# homeboard5.net
KiCad netlist of a schematic drawn in EAGLE
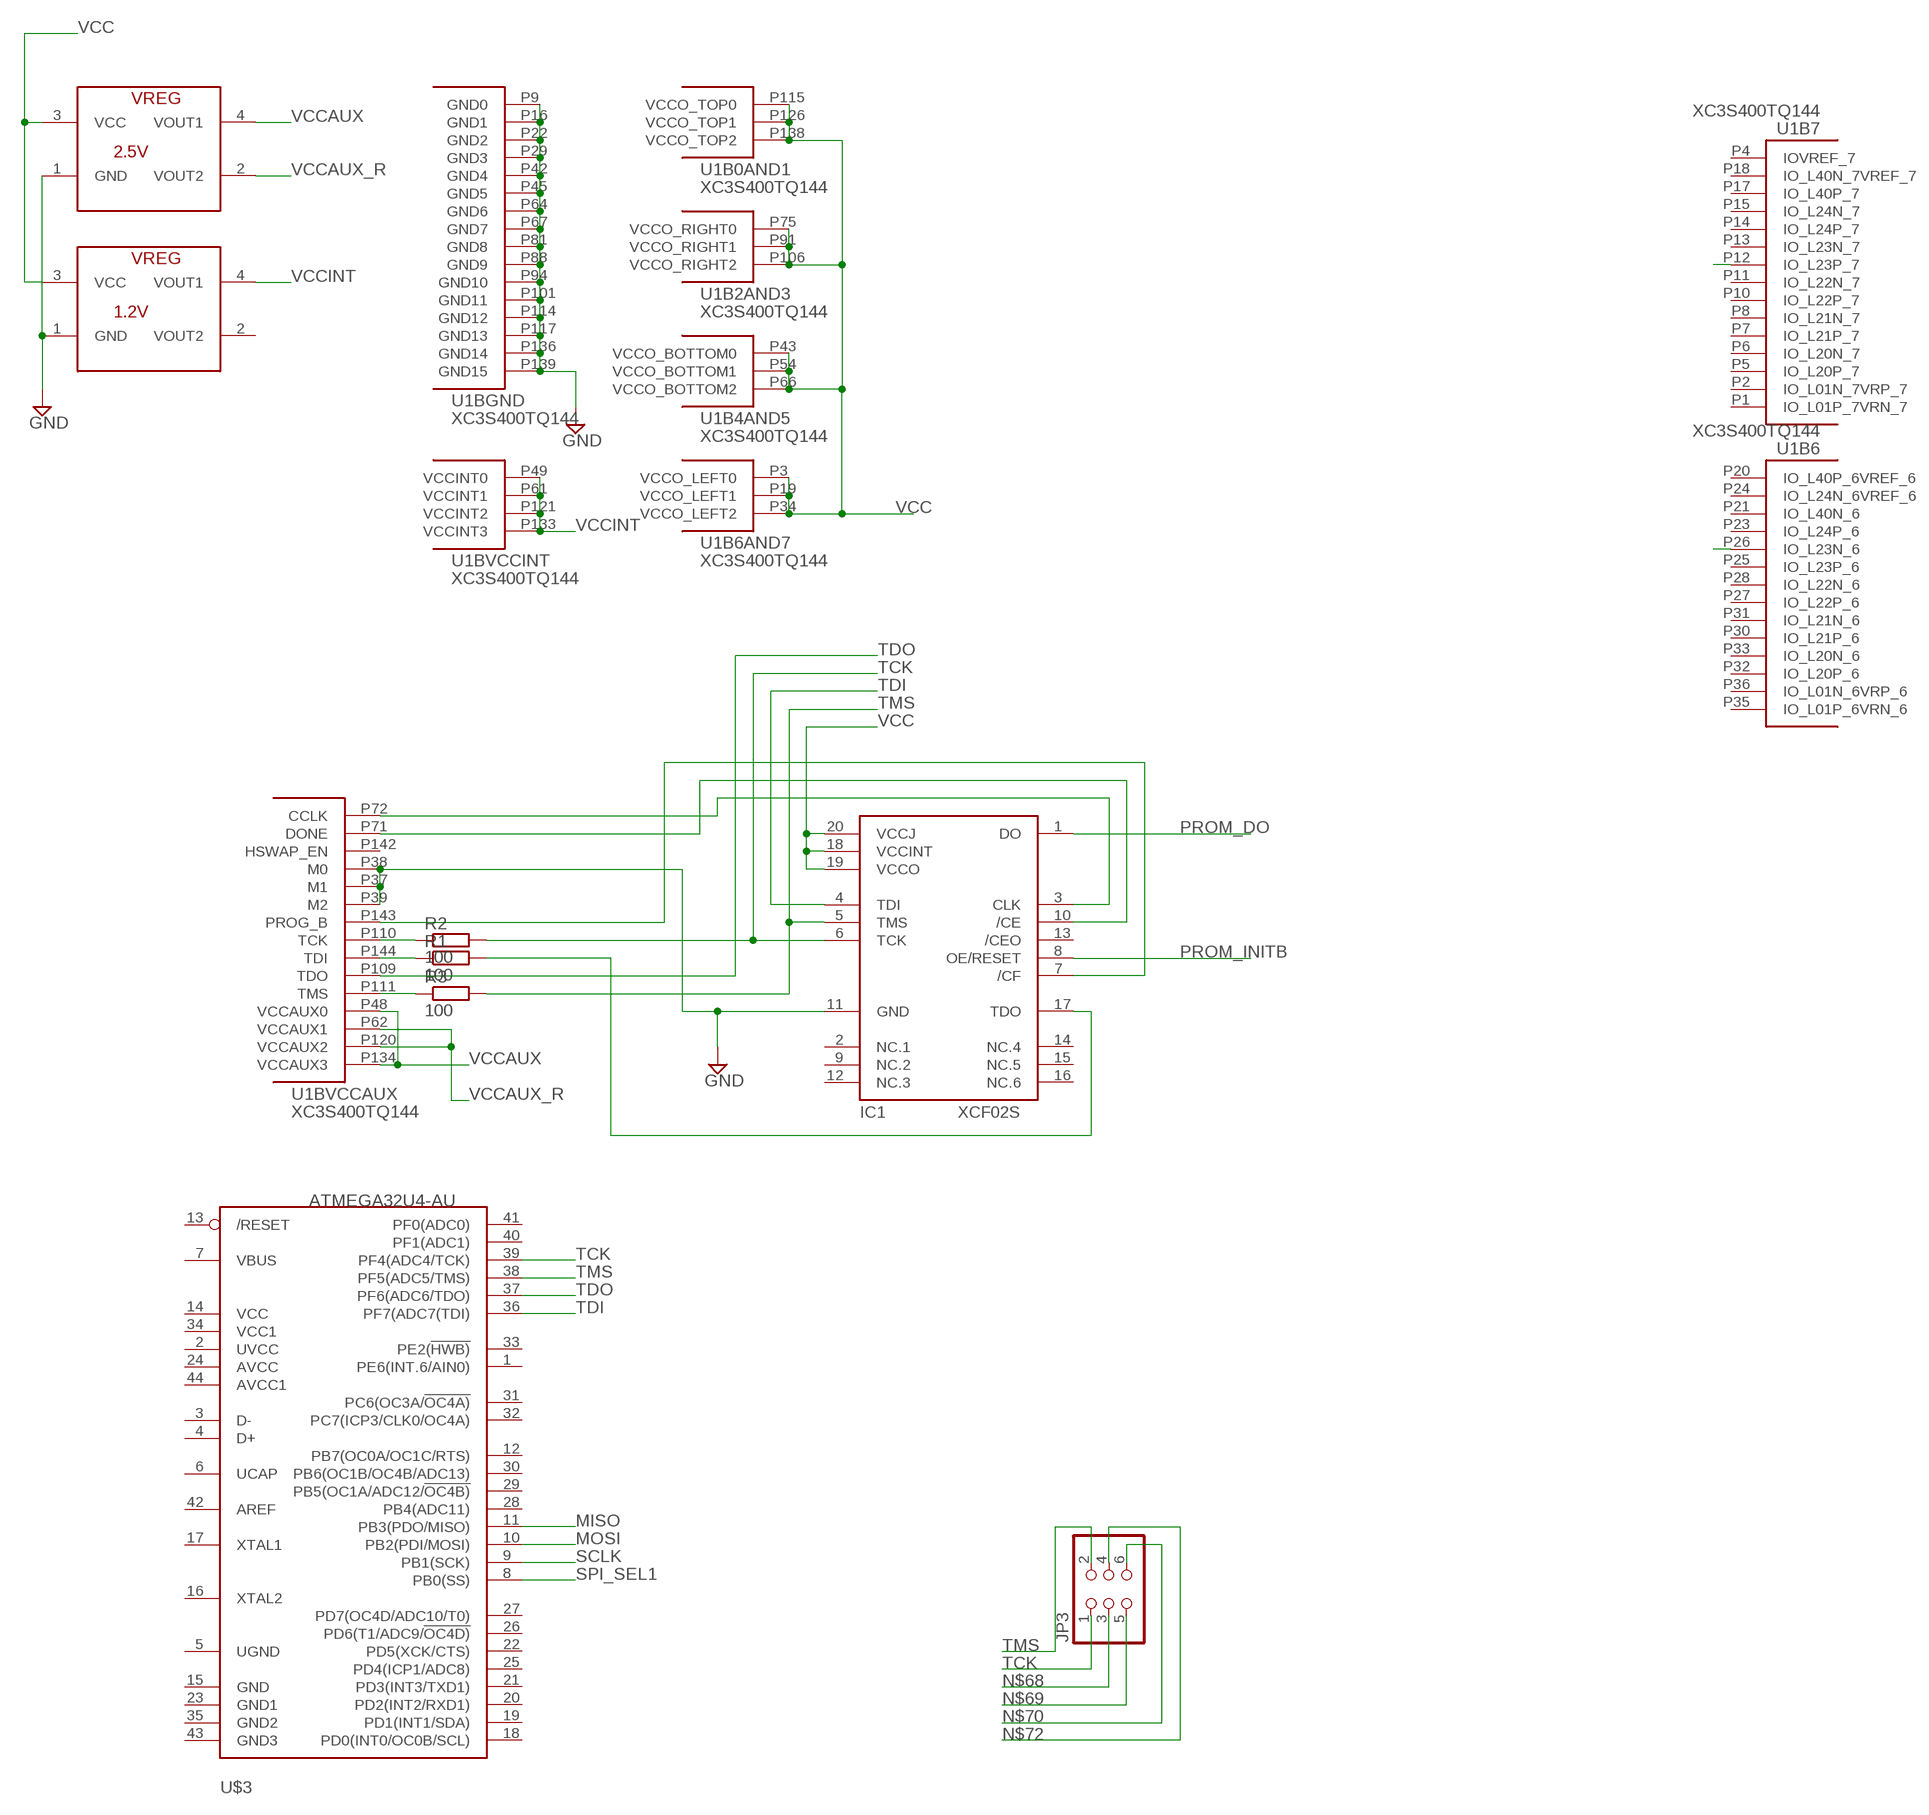
[diagram p0: schematic, sheet 1, part 1 of 3]
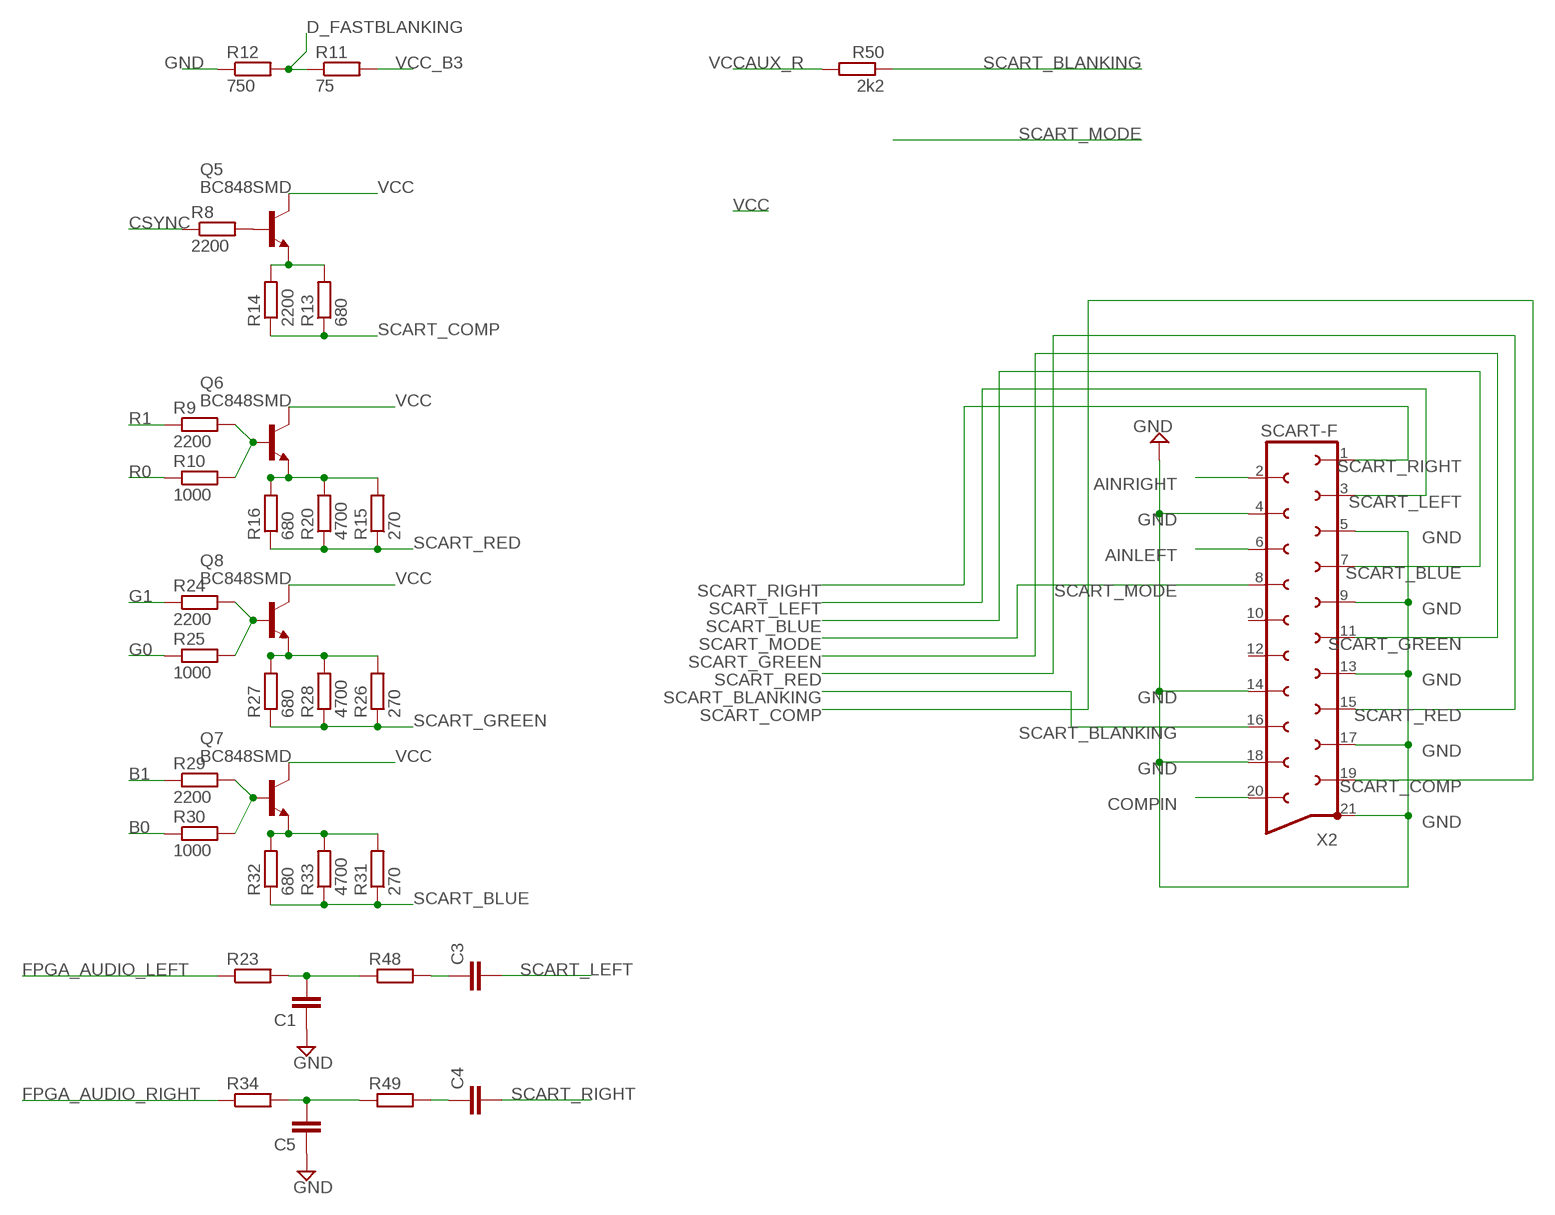
[diagram p1: schematic, sheet 1, part 2 of 3]
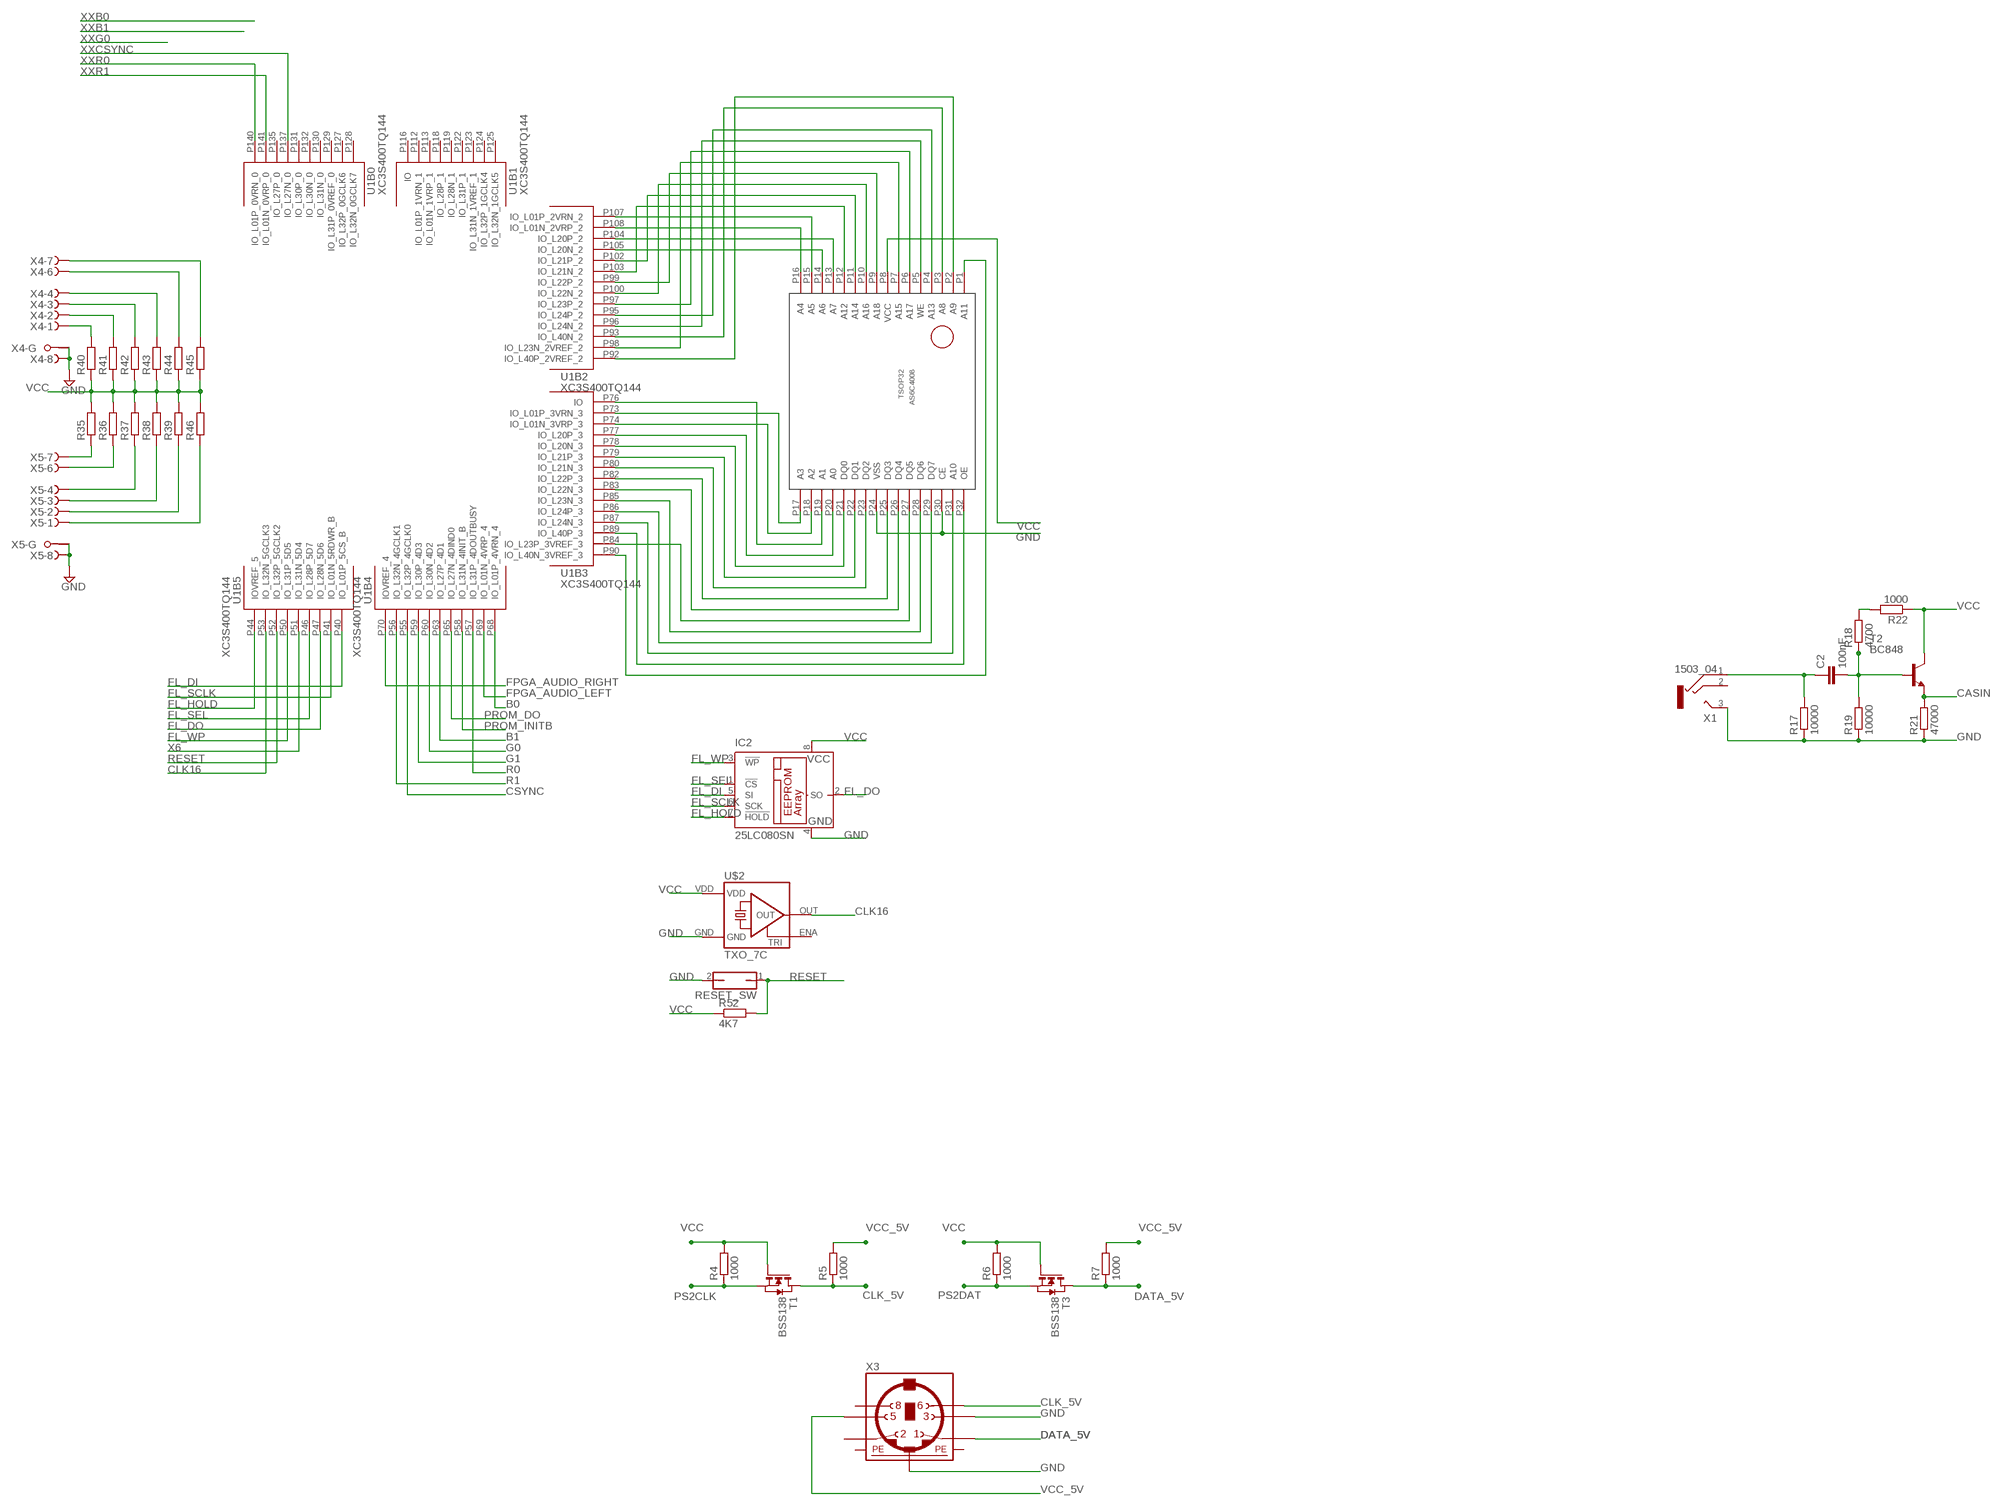
[diagram p2: schematic, sheet 1, part 3 of 3]

(export (version "E")
  (design (tool "Eeschema 10.0.6"))
  (components
    (comp (ref "C1")
      (value "C-EUC0603")
      (footprint "eagle-import:C0603")
      (libsource (lib "eagle-import") (part "C-EUC0603"))
    )
    (comp (ref "C2")
      (value "100nF")
      (footprint "eagle-import:C0603")
      (libsource (lib "eagle-import") (part "C-EUC0603"))
    )
    (comp (ref "C3")
      (value "C-EUC0603")
      (footprint "eagle-import:C0603")
      (libsource (lib "eagle-import") (part "C-EUC0603"))
    )
    (comp (ref "C4")
      (value "C-EUC0603")
      (footprint "eagle-import:C0603")
      (libsource (lib "eagle-import") (part "C-EUC0603"))
    )
    (comp (ref "C5")
      (value "C-EUC0603")
      (footprint "eagle-import:C0603")
      (libsource (lib "eagle-import") (part "C-EUC0603"))
    )
    (comp (ref "IC1")
      (value "XCF02S")
      (footprint "eagle-import:VO20")
      (libsource (lib "eagle-import") (part "XCF02S"))
    )
    (comp (ref "IC2")
      (value "25LC080SN")
      (footprint "eagle-import:SO-08")
      (fields (field (name "MF") "MICROCHIP") (field (name "MPN") "25LC080/SN"))
      (libsource (lib "eagle-import") (part "25SNLC080"))
    )
    (comp (ref "JP3")
      (value "PINHD-2X3")
      (footprint "eagle-import:2X03")
      (libsource (lib "eagle-import") (part "PINHD-2X3"))
    )
    (comp (ref "Q5")
      (value "BC848SMD")
      (footprint "eagle-import:SOT23")
      (libsource (lib "eagle-import") (part "BC848SMD"))
    )
    (comp (ref "Q6")
      (value "BC848SMD")
      (footprint "eagle-import:SOT23")
      (libsource (lib "eagle-import") (part "BC848SMD"))
    )
    (comp (ref "Q7")
      (value "BC848SMD")
      (footprint "eagle-import:SOT23")
      (libsource (lib "eagle-import") (part "BC848SMD"))
    )
    (comp (ref "Q8")
      (value "BC848SMD")
      (footprint "eagle-import:SOT23")
      (libsource (lib "eagle-import") (part "BC848SMD"))
    )
    (comp (ref "R1")
      (value "100")
      (footprint "eagle-import:R0805")
      (libsource (lib "eagle-import") (part "R-EU_R0805"))
    )
    (comp (ref "R2")
      (value "100")
      (footprint "eagle-import:R0805")
      (libsource (lib "eagle-import") (part "R-EU_R0805"))
    )
    (comp (ref "R3")
      (value "100")
      (footprint "eagle-import:R0805")
      (libsource (lib "eagle-import") (part "R-EU_R0805"))
    )
    (comp (ref "R4")
      (value "1000")
      (footprint "eagle-import:R0805")
      (libsource (lib "eagle-import") (part "R-EU_R0805"))
    )
    (comp (ref "R5")
      (value "1000")
      (footprint "eagle-import:R0805")
      (libsource (lib "eagle-import") (part "R-EU_R0805"))
    )
    (comp (ref "R6")
      (value "1000")
      (footprint "eagle-import:R0805")
      (libsource (lib "eagle-import") (part "R-EU_R0805"))
    )
    (comp (ref "R7")
      (value "1000")
      (footprint "eagle-import:R0805")
      (libsource (lib "eagle-import") (part "R-EU_R0805"))
    )
    (comp (ref "R8")
      (value "2200")
      (footprint "eagle-import:R0805")
      (libsource (lib "eagle-import") (part "R-EU_R0805"))
    )
    (comp (ref "R9")
      (value "2200")
      (footprint "eagle-import:R0805")
      (libsource (lib "eagle-import") (part "R-EU_R0805"))
    )
    (comp (ref "R10")
      (value "1000")
      (footprint "eagle-import:R0805")
      (libsource (lib "eagle-import") (part "R-EU_R0805"))
    )
    (comp (ref "R11")
      (value "75")
      (footprint "eagle-import:R0805")
      (libsource (lib "eagle-import") (part "R-EU_R0805"))
    )
    (comp (ref "R12")
      (value "750")
      (footprint "eagle-import:R0805")
      (libsource (lib "eagle-import") (part "R-EU_R0805"))
    )
    (comp (ref "R13")
      (value "680")
      (footprint "eagle-import:R0805")
      (libsource (lib "eagle-import") (part "R-EU_R0805"))
    )
    (comp (ref "R14")
      (value "2200")
      (footprint "eagle-import:R0805")
      (libsource (lib "eagle-import") (part "R-EU_R0805"))
    )
    (comp (ref "R15")
      (value "270")
      (footprint "eagle-import:R0805")
      (libsource (lib "eagle-import") (part "R-EU_R0805"))
    )
    (comp (ref "R16")
      (value "680")
      (footprint "eagle-import:R0805")
      (libsource (lib "eagle-import") (part "R-EU_R0805"))
    )
    (comp (ref "R17")
      (value "10000")
      (footprint "eagle-import:R0805")
      (libsource (lib "eagle-import") (part "R-EU_R0805"))
    )
    (comp (ref "R18")
      (value "4700")
      (footprint "eagle-import:R0805")
      (libsource (lib "eagle-import") (part "R-EU_R0805"))
    )
    (comp (ref "R19")
      (value "10000")
      (footprint "eagle-import:R0805")
      (libsource (lib "eagle-import") (part "R-EU_R0805"))
    )
    (comp (ref "R20")
      (value "4700")
      (footprint "eagle-import:R0805")
      (libsource (lib "eagle-import") (part "R-EU_R0805"))
    )
    (comp (ref "R21")
      (value "47000")
      (footprint "eagle-import:R0805")
      (libsource (lib "eagle-import") (part "R-EU_R0805"))
    )
    (comp (ref "R22")
      (value "1000")
      (footprint "eagle-import:R0805")
      (libsource (lib "eagle-import") (part "R-EU_R0805"))
    )
    (comp (ref "R23")
      (value "R-EU_M0805")
      (footprint "eagle-import:M0805")
      (libsource (lib "eagle-import") (part "resistor_R-EU_M0805"))
    )
    (comp (ref "R24")
      (value "2200")
      (footprint "eagle-import:R0805")
      (libsource (lib "eagle-import") (part "R-EU_R0805"))
    )
    (comp (ref "R25")
      (value "1000")
      (footprint "eagle-import:R0805")
      (libsource (lib "eagle-import") (part "R-EU_R0805"))
    )
    (comp (ref "R26")
      (value "270")
      (footprint "eagle-import:R0805")
      (libsource (lib "eagle-import") (part "R-EU_R0805"))
    )
    (comp (ref "R27")
      (value "680")
      (footprint "eagle-import:R0805")
      (libsource (lib "eagle-import") (part "R-EU_R0805"))
    )
    (comp (ref "R28")
      (value "4700")
      (footprint "eagle-import:R0805")
      (libsource (lib "eagle-import") (part "R-EU_R0805"))
    )
    (comp (ref "R29")
      (value "2200")
      (footprint "eagle-import:R0805")
      (libsource (lib "eagle-import") (part "R-EU_R0805"))
    )
    (comp (ref "R30")
      (value "1000")
      (footprint "eagle-import:R0805")
      (libsource (lib "eagle-import") (part "R-EU_R0805"))
    )
    (comp (ref "R31")
      (value "270")
      (footprint "eagle-import:R0805")
      (libsource (lib "eagle-import") (part "R-EU_R0805"))
    )
    (comp (ref "R32")
      (value "680")
      (footprint "eagle-import:R0805")
      (libsource (lib "eagle-import") (part "R-EU_R0805"))
    )
    (comp (ref "R33")
      (value "4700")
      (footprint "eagle-import:R0805")
      (libsource (lib "eagle-import") (part "R-EU_R0805"))
    )
    (comp (ref "R34")
      (value "R-EU_M0805")
      (footprint "eagle-import:M0805")
      (libsource (lib "eagle-import") (part "resistor_R-EU_M0805"))
    )
    (comp (ref "R35")
      (value "R-EU_M0805")
      (footprint "eagle-import:M0805")
      (libsource (lib "eagle-import") (part "resistor_R-EU_M0805"))
    )
    (comp (ref "R36")
      (value "R-EU_M0805")
      (footprint "eagle-import:M0805")
      (libsource (lib "eagle-import") (part "resistor_R-EU_M0805"))
    )
    (comp (ref "R37")
      (value "R-EU_M0805")
      (footprint "eagle-import:M0805")
      (libsource (lib "eagle-import") (part "resistor_R-EU_M0805"))
    )
    (comp (ref "R38")
      (value "R-EU_M0805")
      (footprint "eagle-import:M0805")
      (libsource (lib "eagle-import") (part "resistor_R-EU_M0805"))
    )
    (comp (ref "R39")
      (value "R-EU_M0805")
      (footprint "eagle-import:M0805")
      (libsource (lib "eagle-import") (part "resistor_R-EU_M0805"))
    )
    (comp (ref "R40")
      (value "R-EU_M0805")
      (footprint "eagle-import:M0805")
      (libsource (lib "eagle-import") (part "resistor_R-EU_M0805"))
    )
    (comp (ref "R41")
      (value "R-EU_M0805")
      (footprint "eagle-import:M0805")
      (libsource (lib "eagle-import") (part "resistor_R-EU_M0805"))
    )
    (comp (ref "R42")
      (value "R-EU_M0805")
      (footprint "eagle-import:M0805")
      (libsource (lib "eagle-import") (part "resistor_R-EU_M0805"))
    )
    (comp (ref "R43")
      (value "R-EU_M0805")
      (footprint "eagle-import:M0805")
      (libsource (lib "eagle-import") (part "resistor_R-EU_M0805"))
    )
    (comp (ref "R44")
      (value "R-EU_M0805")
      (footprint "eagle-import:M0805")
      (libsource (lib "eagle-import") (part "resistor_R-EU_M0805"))
    )
    (comp (ref "R45")
      (value "R-EU_M0805")
      (footprint "eagle-import:M0805")
      (libsource (lib "eagle-import") (part "resistor_R-EU_M0805"))
    )
    (comp (ref "R46")
      (value "R-EU_M0805")
      (footprint "eagle-import:M0805")
      (libsource (lib "eagle-import") (part "resistor_R-EU_M0805"))
    )
    (comp (ref "R48")
      (value "R-EU_M0805")
      (footprint "eagle-import:M0805")
      (libsource (lib "eagle-import") (part "resistor_R-EU_M0805"))
    )
    (comp (ref "R49")
      (value "R-EU_M0805")
      (footprint "eagle-import:M0805")
      (libsource (lib "eagle-import") (part "resistor_R-EU_M0805"))
    )
    (comp (ref "R50")
      (value "2k2")
      (footprint "eagle-import:M0805")
      (libsource (lib "eagle-import") (part "resistor_R-EU_M0805"))
    )
    (comp (ref "R52")
      (value "4K7")
      (footprint "eagle-import:M0805")
      (libsource (lib "eagle-import") (part "resistor_R-EU_M0805"))
    )
    (comp (ref "REG1.2")
      (value "1.2V")
      (footprint "eagle-import:SOT223")
      (libsource (lib "eagle-import") (part "NX1117"))
    )
    (comp (ref "REG2.5")
      (value "2.5V")
      (footprint "eagle-import:SOT223")
      (libsource (lib "eagle-import") (part "NX1117"))
    )
    (comp (ref "RESET_SW")
      (value "JP1Q")
      (footprint "eagle-import:JP1")
      (libsource (lib "eagle-import") (part "JP1Q"))
    )
    (comp (ref "T1")
      (value "BSS138")
      (footprint "eagle-import:SOT-23")
      (libsource (lib "eagle-import") (part "NMOSSOT23"))
    )
    (comp (ref "T2")
      (value "BC848")
      (footprint "eagle-import:SOT23")
      (libsource (lib "eagle-import") (part "BC848"))
    )
    (comp (ref "T3")
      (value "BSS138")
      (footprint "eagle-import:SOT-23")
      (libsource (lib "eagle-import") (part "NMOSSOT23"))
    )
    (comp (ref "U$1")
      (value "AS6C4008")
      (footprint "eagle-import:TSOP32")
      (libsource (lib "eagle-import") (part "AS6C4008"))
    )
    (comp (ref "U$2")
      (value "TXO_7C")
      (footprint "eagle-import:OSC_7C")
      (libsource (lib "eagle-import") (part "TXO_7C"))
    )
    (comp (ref "U$3")
      (value "ATMEGA32U4-AU")
      (footprint "eagle-import:TQFP44")
      (libsource (lib "eagle-import") (part "ATMEGA32U4-AU"))
    )
    (comp (ref "U1")
      (value "XC3S400TQ144")
      (footprint "eagle-import:TQ144")
      (libsource (lib "eagle-import") (part "XC3S400TQ144"))
    )
    (comp (ref "X1")
      (value "1503_04")
      (footprint "eagle-import:1503_04")
      (libsource (lib "eagle-import") (part "1503_04"))
    )
    (comp (ref "X2")
      (value "SCART-F")
      (footprint "eagle-import:SCART-F")
      (libsource (lib "eagle-import") (part "SCART-F"))
    )
    (comp (ref "X3")
      (value "MINI_DIN_6")
      (footprint "eagle-import:M_DIN6")
      (libsource (lib "eagle-import") (part "MINI_DIN_6"))
    )
    (comp (ref "X4")
      (value "F09HPS")
      (footprint "eagle-import:F09HP")
      (libsource (lib "eagle-import") (part "F09HPS"))
    )
    (comp (ref "X5")
      (value "F09HPS")
      (footprint "eagle-import:F09HP")
      (libsource (lib "eagle-import") (part "F09HPS"))
    )
  )
  (nets
    (net (code "1") (name "/AINLEFT") (class "Default")
      (node (ref "X2") (pin "6") (pinfunction "6_6") (pintype "passive"))
    )
    (net (code "2") (name "/AINRIGHT") (class "Default")
      (node (ref "X2") (pin "2") (pinfunction "2_2") (pintype "passive"))
    )
    (net (code "3") (name "/B0") (class "Default")
      (node (ref "R30") (pin "1") (pinfunction "1_1") (pintype "passive"))
      (node (ref "U1") (pin "P68") (pinfunction "IO_L01P_4VRN_4_P68") (pintype "bidirectional"))
    )
    (net (code "4") (name "/B1") (class "Default")
      (node (ref "R29") (pin "1") (pinfunction "1_1") (pintype "passive"))
      (node (ref "U1") (pin "P63") (pinfunction "IO_L27P_4D1_P63") (pintype "bidirectional"))
    )
    (net (code "5") (name "/CASIN") (class "Default")
      (node (ref "R21") (pin "2") (pinfunction "2_2") (pintype "passive"))
      (node (ref "T2") (pin "2") (pinfunction "E_2") (pintype "passive"))
    )
    (net (code "6") (name "/CLK16") (class "Default")
      (node (ref "U$2") (pin "OUT") (pinfunction "OUT_OUT") (pintype "output"))
      (node (ref "U1") (pin "P53") (pinfunction "IO_L32N_5GCLK3_P53") (pintype "bidirectional"))
    )
    (net (code "7") (name "/CLK_5V") (class "Default")
      (node (ref "R5") (pin "1") (pinfunction "1_1") (pintype "passive"))
      (node (ref "T1") (pin "1") (pinfunction "D_1") (pintype "passive"))
      (node (ref "X3") (pin "6") (pinfunction "6_6") (pintype "passive"))
    )
    (net (code "8") (name "/COMPIN") (class "Default")
      (node (ref "X2") (pin "20") (pinfunction "20_20") (pintype "passive"))
    )
    (net (code "9") (name "/CSYNC") (class "Default")
      (node (ref "R8") (pin "1") (pinfunction "1_1") (pintype "passive"))
      (node (ref "U1") (pin "P55") (pinfunction "IO_L32P_4GCLK0_P55") (pintype "bidirectional"))
    )
    (net (code "10") (name "/DATA_5V") (class "Default")
      (node (ref "R7") (pin "1") (pinfunction "1_1") (pintype "passive"))
      (node (ref "T3") (pin "1") (pinfunction "D_1") (pintype "passive"))
      (node (ref "X3") (pin "1") (pinfunction "1_1") (pintype "passive"))
    )
    (net (code "11") (name "/D_FASTBLANKING") (class "Default")
      (node (ref "R11") (pin "1") (pinfunction "1_1") (pintype "passive"))
      (node (ref "R12") (pin "2") (pinfunction "2_2") (pintype "passive"))
    )
    (net (code "12") (name "/FL_DI") (class "Default")
      (node (ref "IC2") (pin "5") (pinfunction "SI_5") (pintype "input"))
      (node (ref "U1") (pin "P40") (pinfunction "IO_L01P_5CS_B_P40") (pintype "bidirectional"))
    )
    (net (code "13") (name "/FL_DO") (class "Default")
      (node (ref "IC2") (pin "2") (pinfunction "SO_2") (pintype "bidirectional"))
      (node (ref "U1") (pin "P47") (pinfunction "IO_L28N_5D6_P47") (pintype "bidirectional"))
    )
    (net (code "14") (name "/FL_HOLD") (class "Default")
      (node (ref "IC2") (pin "7") (pinfunction "~{HOLD}_7") (pintype "input"))
      (node (ref "U1") (pin "P44") (pinfunction "IOVREF_5_P44") (pintype "bidirectional"))
    )
    (net (code "15") (name "/FL_SCLK") (class "Default")
      (node (ref "IC2") (pin "6") (pinfunction "SCK_6") (pintype "input"))
      (node (ref "U1") (pin "P41") (pinfunction "IO_L01N_5RDWR_B_P41") (pintype "bidirectional"))
    )
    (net (code "16") (name "/FL_SEL") (class "Default")
      (node (ref "IC2") (pin "1") (pinfunction "~{CS}_1") (pintype "input"))
      (node (ref "U1") (pin "P46") (pinfunction "IO_L28P_5D7_P46") (pintype "bidirectional"))
    )
    (net (code "17") (name "/FL_WP") (class "Default")
      (node (ref "IC2") (pin "3") (pinfunction "~{WP}_3") (pintype "input"))
      (node (ref "U1") (pin "P50") (pinfunction "IO_L31P_5D5_P50") (pintype "bidirectional"))
    )
    (net (code "18") (name "/FPGA_AUDIO_LEFT") (class "Default")
      (node (ref "R23") (pin "1") (pinfunction "1_1") (pintype "passive"))
      (node (ref "U1") (pin "P69") (pinfunction "IO_L01N_4VRP_4_P69") (pintype "bidirectional"))
    )
    (net (code "19") (name "/FPGA_AUDIO_RIGHT") (class "Default")
      (node (ref "R34") (pin "1") (pinfunction "1_1") (pintype "passive"))
      (node (ref "U1") (pin "P70") (pinfunction "IOVREF_4_P70") (pintype "bidirectional"))
    )
    (net (code "20") (name "/G0") (class "Default")
      (node (ref "R25") (pin "1") (pinfunction "1_1") (pintype "passive"))
      (node (ref "U1") (pin "P60") (pinfunction "IO_L30N_4D2_P60") (pintype "bidirectional"))
    )
    (net (code "21") (name "/G1") (class "Default")
      (node (ref "R24") (pin "1") (pinfunction "1_1") (pintype "passive"))
      (node (ref "U1") (pin "P59") (pinfunction "IO_L30P_4D3_P59") (pintype "bidirectional"))
    )
    (net (code "22") (name "/MISO") (class "Default")
      (node (ref "U$3") (pin "11") (pinfunction "PB3(PDO/MISO)_11") (pintype "bidirectional"))
    )
    (net (code "23") (name "/MOSI") (class "Default")
      (node (ref "U$3") (pin "10") (pinfunction "PB2(PDI/MOSI)_10") (pintype "bidirectional"))
    )
    (net (code "24") (name "/N$68") (class "Default")
      (node (ref "JP3") (pin "3") (pinfunction "3_3") (pintype "passive"))
    )
    (net (code "25") (name "/N$69") (class "Default")
      (node (ref "JP3") (pin "5") (pinfunction "5_5") (pintype "passive"))
    )
    (net (code "26") (name "/N$70") (class "Default")
      (node (ref "JP3") (pin "6") (pinfunction "6_6") (pintype "passive"))
    )
    (net (code "27") (name "/N$72") (class "Default")
      (node (ref "JP3") (pin "4") (pinfunction "4_4") (pintype "passive"))
    )
    (net (code "28") (name "/PE1") (class "Default")
      (node (ref "X3") (pin "SH1") (pinfunction "PE1_SH1") (pintype "power_in"))
    )
    (net (code "29") (name "/PE3") (class "Default")
      (node (ref "X3") (pin "SH3") (pinfunction "PE3_SH3") (pintype "power_in"))
    )
    (net (code "30") (name "/PROM_DO") (class "Default")
      (node (ref "IC1") (pin "1") (pinfunction "DO_1") (pintype "bidirectional"))
      (node (ref "U1") (pin "P65") (pinfunction "IO_L27N_4DIND0_P65") (pintype "bidirectional"))
    )
    (net (code "31") (name "/PROM_INITB") (class "Default")
      (node (ref "IC1") (pin "8") (pinfunction "OE/RESET_8") (pintype "bidirectional"))
      (node (ref "U1") (pin "P58") (pinfunction "IO_L31N_4INIT_B_P58") (pintype "bidirectional"))
    )
    (net (code "32") (name "/PS2CLK") (class "Default")
      (node (ref "R4") (pin "1") (pinfunction "1_1") (pintype "passive"))
      (node (ref "T1") (pin "2") (pinfunction "S_2") (pintype "passive"))
    )
    (net (code "33") (name "/PS2DAT") (class "Default")
      (node (ref "R6") (pin "1") (pinfunction "1_1") (pintype "passive"))
      (node (ref "T3") (pin "2") (pinfunction "S_2") (pintype "passive"))
    )
    (net (code "34") (name "/R0") (class "Default")
      (node (ref "R10") (pin "1") (pinfunction "1_1") (pintype "passive"))
      (node (ref "U1") (pin "P57") (pinfunction "IO_L31P_4DOUTBUSY_P57") (pintype "bidirectional"))
    )
    (net (code "35") (name "/R1") (class "Default")
      (node (ref "R9") (pin "1") (pinfunction "1_1") (pintype "passive"))
      (node (ref "U1") (pin "P56") (pinfunction "IO_L32N_4GCLK1_P56") (pintype "bidirectional"))
    )
    (net (code "36") (name "/RESET") (class "Default")
      (node (ref "R52") (pin "2") (pinfunction "2_2") (pintype "passive"))
      (node (ref "RESET_SW") (pin "1") (pinfunction "1_1") (pintype "passive"))
      (node (ref "U1") (pin "P52") (pinfunction "IO_L32P_5GCLK2_P52") (pintype "bidirectional"))
    )
    (net (code "37") (name "/SCART_BLANKING") (class "Default")
      (node (ref "R50") (pin "1") (pinfunction "1_1") (pintype "passive"))
      (node (ref "X2") (pin "16") (pinfunction "16_16") (pintype "passive"))
    )
    (net (code "38") (name "/SCART_BLUE") (class "Default")
      (node (ref "R31") (pin "1") (pinfunction "1_1") (pintype "passive"))
      (node (ref "R32") (pin "1") (pinfunction "1_1") (pintype "passive"))
      (node (ref "R33") (pin "1") (pinfunction "1_1") (pintype "passive"))
      (node (ref "X2") (pin "7") (pinfunction "7_7") (pintype "passive"))
    )
    (net (code "39") (name "/SCART_COMP") (class "Default")
      (node (ref "R13") (pin "1") (pinfunction "1_1") (pintype "passive"))
      (node (ref "R14") (pin "1") (pinfunction "1_1") (pintype "passive"))
      (node (ref "X2") (pin "19") (pinfunction "19_19") (pintype "passive"))
    )
    (net (code "40") (name "/SCART_GREEN") (class "Default")
      (node (ref "R26") (pin "1") (pinfunction "1_1") (pintype "passive"))
      (node (ref "R27") (pin "1") (pinfunction "1_1") (pintype "passive"))
      (node (ref "R28") (pin "1") (pinfunction "1_1") (pintype "passive"))
      (node (ref "X2") (pin "11") (pinfunction "11_11") (pintype "passive"))
    )
    (net (code "41") (name "/SCART_LEFT") (class "Default")
      (node (ref "C3") (pin "2") (pinfunction "2_2") (pintype "passive"))
      (node (ref "X2") (pin "3") (pinfunction "3_3") (pintype "passive"))
    )
    (net (code "42") (name "/SCART_MODE") (class "Default")
      (node (ref "X2") (pin "8") (pinfunction "8_8") (pintype "passive"))
    )
    (net (code "43") (name "/SCART_RED") (class "Default")
      (node (ref "R15") (pin "1") (pinfunction "1_1") (pintype "passive"))
      (node (ref "R16") (pin "1") (pinfunction "1_1") (pintype "passive"))
      (node (ref "R20") (pin "1") (pinfunction "1_1") (pintype "passive"))
      (node (ref "X2") (pin "15") (pinfunction "15_15") (pintype "passive"))
    )
    (net (code "44") (name "/SCART_RIGHT") (class "Default")
      (node (ref "C4") (pin "2") (pinfunction "2_2") (pintype "passive"))
      (node (ref "X2") (pin "1") (pinfunction "1_1") (pintype "passive"))
    )
    (net (code "45") (name "/SCLK") (class "Default")
      (node (ref "U$3") (pin "9") (pinfunction "PB1(SCK)_9") (pintype "bidirectional"))
    )
    (net (code "46") (name "/SPI_SEL1") (class "Default")
      (node (ref "U$3") (pin "8") (pinfunction "PB0(SS)_8") (pintype "bidirectional"))
    )
    (net (code "47") (name "/TCK") (class "Default")
      (node (ref "IC1") (pin "6") (pinfunction "TCK_6") (pintype "bidirectional"))
      (node (ref "JP3") (pin "1") (pinfunction "1_1") (pintype "passive"))
      (node (ref "R2") (pin "2") (pinfunction "2_2") (pintype "passive"))
      (node (ref "U$3") (pin "39") (pinfunction "PF4(ADC4/TCK)_39") (pintype "bidirectional"))
    )
    (net (code "48") (name "/TDI") (class "Default")
      (node (ref "IC1") (pin "4") (pinfunction "TDI_4") (pintype "bidirectional"))
      (node (ref "U$3") (pin "36") (pinfunction "PF7(ADC7(TDI)_36") (pintype "bidirectional"))
    )
    (net (code "49") (name "/TDO") (class "Default")
      (node (ref "U$3") (pin "37") (pinfunction "PF6(ADC6/TDO)_37") (pintype "bidirectional"))
      (node (ref "U1") (pin "P109") (pinfunction "TDO_P109") (pintype "bidirectional"))
    )
    (net (code "50") (name "/TMS") (class "Default")
      (node (ref "IC1") (pin "5") (pinfunction "TMS_5") (pintype "bidirectional"))
      (node (ref "JP3") (pin "2") (pinfunction "2_2") (pintype "passive"))
      (node (ref "R3") (pin "2") (pinfunction "2_2") (pintype "passive"))
      (node (ref "U$3") (pin "38") (pinfunction "PF5(ADC5/TMS)_38") (pintype "bidirectional"))
    )
    (net (code "51") (name "/VCC") (class "Default")
      (node (ref "IC1") (pin "18") (pinfunction "VCCINT_18") (pintype "bidirectional"))
      (node (ref "IC1") (pin "19") (pinfunction "VCCO_19") (pintype "bidirectional"))
      (node (ref "IC1") (pin "20") (pinfunction "VCCJ_20") (pintype "bidirectional"))
      (node (ref "IC2") (pin "8") (pinfunction "VCC_8") (pintype "power_in"))
      (node (ref "Q5") (pin "3") (pinfunction "C_3") (pintype "passive"))
      (node (ref "Q6") (pin "3") (pinfunction "C_3") (pintype "passive"))
      (node (ref "Q7") (pin "3") (pinfunction "C_3") (pintype "passive"))
      (node (ref "Q8") (pin "3") (pinfunction "C_3") (pintype "passive"))
      (node (ref "R22") (pin "1") (pinfunction "1_1") (pintype "passive"))
      (node (ref "R35") (pin "2") (pinfunction "2_2") (pintype "passive"))
      (node (ref "R36") (pin "2") (pinfunction "2_2") (pintype "passive"))
      (node (ref "R37") (pin "2") (pinfunction "2_2") (pintype "passive"))
      (node (ref "R38") (pin "2") (pinfunction "2_2") (pintype "passive"))
      (node (ref "R39") (pin "2") (pinfunction "2_2") (pintype "passive"))
      (node (ref "R4") (pin "2") (pinfunction "2_2") (pintype "passive"))
      (node (ref "R40") (pin "1") (pinfunction "1_1") (pintype "passive"))
      (node (ref "R41") (pin "1") (pinfunction "1_1") (pintype "passive"))
      (node (ref "R42") (pin "1") (pinfunction "1_1") (pintype "passive"))
      (node (ref "R43") (pin "1") (pinfunction "1_1") (pintype "passive"))
      (node (ref "R44") (pin "1") (pinfunction "1_1") (pintype "passive"))
      (node (ref "R45") (pin "1") (pinfunction "1_1") (pintype "passive"))
      (node (ref "R46") (pin "2") (pinfunction "2_2") (pintype "passive"))
      (node (ref "R52") (pin "1") (pinfunction "1_1") (pintype "passive"))
      (node (ref "R6") (pin "2") (pinfunction "2_2") (pintype "passive"))
      (node (ref "REG1.2") (pin "3") (pinfunction "VCC_3") (pintype "bidirectional"))
      (node (ref "REG2.5") (pin "3") (pinfunction "VCC_3") (pintype "bidirectional"))
      (node (ref "T1") (pin "3") (pinfunction "G_3") (pintype "passive"))
      (node (ref "T2") (pin "3") (pinfunction "C_3") (pintype "passive"))
      (node (ref "T3") (pin "3") (pinfunction "G_3") (pintype "passive"))
      (node (ref "U$1") (pin "P8") (pinfunction "VCC_P8") (pintype "bidirectional"))
      (node (ref "U$2") (pin "VDD") (pinfunction "VDD_VDD") (pintype "power_in"))
      (node (ref "U1") (pin "P106") (pinfunction "VCCO_RIGHT2_P106") (pintype "passive"))
      (node (ref "U1") (pin "P115") (pinfunction "VCCO_TOP0_P115") (pintype "passive"))
      (node (ref "U1") (pin "P126") (pinfunction "VCCO_TOP1_P126") (pintype "passive"))
      (node (ref "U1") (pin "P138") (pinfunction "VCCO_TOP2_P138") (pintype "passive"))
      (node (ref "U1") (pin "P19") (pinfunction "VCCO_LEFT1_P19") (pintype "passive"))
      (node (ref "U1") (pin "P3") (pinfunction "VCCO_LEFT0_P3") (pintype "passive"))
      (node (ref "U1") (pin "P34") (pinfunction "VCCO_LEFT2_P34") (pintype "passive"))
      (node (ref "U1") (pin "P43") (pinfunction "VCCO_BOTTOM0_P43") (pintype "passive"))
      (node (ref "U1") (pin "P54") (pinfunction "VCCO_BOTTOM1_P54") (pintype "passive"))
      (node (ref "U1") (pin "P66") (pinfunction "VCCO_BOTTOM2_P66") (pintype "passive"))
      (node (ref "U1") (pin "P75") (pinfunction "VCCO_RIGHT0_P75") (pintype "passive"))
      (node (ref "U1") (pin "P91") (pinfunction "VCCO_RIGHT1_P91") (pintype "passive"))
    )
    (net (code "52") (name "/VCCAUX") (class "Default")
      (node (ref "REG2.5") (pin "4") (pinfunction "VOUT1_4") (pintype "bidirectional"))
      (node (ref "U1") (pin "P134") (pinfunction "VCCAUX3_P134") (pintype "passive"))
      (node (ref "U1") (pin "P48") (pinfunction "VCCAUX0_P48") (pintype "passive"))
    )
    (net (code "53") (name "/VCCAUX_R") (class "Default")
      (node (ref "R50") (pin "2") (pinfunction "2_2") (pintype "passive"))
      (node (ref "REG2.5") (pin "2") (pinfunction "VOUT2_2") (pintype "bidirectional"))
      (node (ref "U1") (pin "P120") (pinfunction "VCCAUX2_P120") (pintype "passive"))
      (node (ref "U1") (pin "P62") (pinfunction "VCCAUX1_P62") (pintype "passive"))
    )
    (net (code "54") (name "/VCCINT") (class "Default")
      (node (ref "REG1.2") (pin "4") (pinfunction "VOUT1_4") (pintype "bidirectional"))
      (node (ref "U1") (pin "P121") (pinfunction "VCCINT2_P121") (pintype "passive"))
      (node (ref "U1") (pin "P133") (pinfunction "VCCINT3_P133") (pintype "passive"))
      (node (ref "U1") (pin "P49") (pinfunction "VCCINT0_P49") (pintype "passive"))
      (node (ref "U1") (pin "P61") (pinfunction "VCCINT1_P61") (pintype "passive"))
    )
    (net (code "55") (name "/VCC_5V") (class "Default")
      (node (ref "R5") (pin "2") (pinfunction "2_2") (pintype "passive"))
      (node (ref "R7") (pin "2") (pinfunction "2_2") (pintype "passive"))
      (node (ref "X3") (pin "5") (pinfunction "5_5") (pintype "passive"))
    )
    (net (code "56") (name "/VCC_B3") (class "Default")
      (node (ref "R11") (pin "2") (pinfunction "2_2") (pintype "passive"))
    )
    (net (code "57") (name "/X6") (class "Default")
      (node (ref "U1") (pin "P51") (pinfunction "IO_L31N_5D4_P51") (pintype "bidirectional"))
    )
    (net (code "60") (name "/XXCSYNC") (class "Default")
      (node (ref "U1") (pin "P137") (pinfunction "IO_L27N_0_P137") (pintype "bidirectional"))
    )
    (net (code "62") (name "/XXR0") (class "Default")
      (node (ref "U1") (pin "P140") (pinfunction "IO_L01P_0VRN_0_P140") (pintype "bidirectional"))
    )
    (net (code "63") (name "/XXR1") (class "Default")
      (node (ref "U1") (pin "P141") (pinfunction "IO_L01N_0VRP_0_P141") (pintype "bidirectional"))
    )
    (net (code "64") (name "GND") (class "Default")
      (node (ref "C1") (pin "1") (pinfunction "1_1") (pintype "passive"))
      (node (ref "C5") (pin "1") (pinfunction "1_1") (pintype "passive"))
      (node (ref "IC1") (pin "11") (pinfunction "GND_11") (pintype "bidirectional"))
      (node (ref "IC2") (pin "4") (pinfunction "GND_4") (pintype "power_in"))
      (node (ref "R12") (pin "1") (pinfunction "1_1") (pintype "passive"))
      (node (ref "R17") (pin "1") (pinfunction "1_1") (pintype "passive"))
      (node (ref "R19") (pin "1") (pinfunction "1_1") (pintype "passive"))
      (node (ref "R21") (pin "1") (pinfunction "1_1") (pintype "passive"))
      (node (ref "REG1.2") (pin "1") (pinfunction "GND_1") (pintype "bidirectional"))
      (node (ref "REG2.5") (pin "1") (pinfunction "GND_1") (pintype "bidirectional"))
      (node (ref "RESET_SW") (pin "2") (pinfunction "2_2") (pintype "passive"))
      (node (ref "U$1") (pin "P24") (pinfunction "VSS_P24") (pintype "bidirectional"))
      (node (ref "U$1") (pin "P30") (pinfunction "CE_P30") (pintype "bidirectional"))
      (node (ref "U$2") (pin "GND") (pinfunction "GND_GND") (pintype "power_in"))
      (node (ref "U1") (pin "P101") (pinfunction "GND11_P101") (pintype "passive"))
      (node (ref "U1") (pin "P114") (pinfunction "GND12_P114") (pintype "passive"))
      (node (ref "U1") (pin "P117") (pinfunction "GND13_P117") (pintype "passive"))
      (node (ref "U1") (pin "P136") (pinfunction "GND14_P136") (pintype "passive"))
      (node (ref "U1") (pin "P139") (pinfunction "GND15_P139") (pintype "passive"))
      (node (ref "U1") (pin "P16") (pinfunction "GND1_P16") (pintype "passive"))
      (node (ref "U1") (pin "P22") (pinfunction "GND2_P22") (pintype "passive"))
      (node (ref "U1") (pin "P29") (pinfunction "GND3_P29") (pintype "passive"))
      (node (ref "U1") (pin "P37") (pinfunction "M1_P37") (pintype "bidirectional"))
      (node (ref "U1") (pin "P38") (pinfunction "M0_P38") (pintype "bidirectional"))
      (node (ref "U1") (pin "P39") (pinfunction "M2_P39") (pintype "bidirectional"))
      (node (ref "U1") (pin "P42") (pinfunction "GND4_P42") (pintype "passive"))
      (node (ref "U1") (pin "P45") (pinfunction "GND5_P45") (pintype "passive"))
      (node (ref "U1") (pin "P64") (pinfunction "GND6_P64") (pintype "passive"))
      (node (ref "U1") (pin "P67") (pinfunction "GND7_P67") (pintype "passive"))
      (node (ref "U1") (pin "P81") (pinfunction "GND8_P81") (pintype "passive"))
      (node (ref "U1") (pin "P88") (pinfunction "GND9_P88") (pintype "passive"))
      (node (ref "U1") (pin "P9") (pinfunction "GND0_P9") (pintype "passive"))
      (node (ref "U1") (pin "P94") (pinfunction "GND10_P94") (pintype "passive"))
      (node (ref "X1") (pin "3") (pinfunction "2_3") (pintype "passive"))
      (node (ref "X2") (pin "13") (pinfunction "13_13") (pintype "passive"))
      (node (ref "X2") (pin "14") (pinfunction "14_14") (pintype "passive"))
      (node (ref "X2") (pin "17") (pinfunction "17_17") (pintype "passive"))
      (node (ref "X2") (pin "18") (pinfunction "18_18") (pintype "passive"))
      (node (ref "X2") (pin "21") (pinfunction "21_21") (pintype "passive"))
      (node (ref "X2") (pin "4") (pinfunction "4_4") (pintype "passive"))
      (node (ref "X2") (pin "5") (pinfunction "5_5") (pintype "passive"))
      (node (ref "X2") (pin "9") (pinfunction "9_9") (pintype "passive"))
      (node (ref "X3") (pin "3") (pinfunction "3_3") (pintype "passive"))
      (node (ref "X3") (pin "SH2") (pinfunction "PE2_SH2") (pintype "power_in"))
      (node (ref "X4") (pin "8") (pinfunction "F_8") (pintype "passive"))
      (node (ref "X4") (pin "G1") (pinfunction "G1_G1") (pintype "passive"))
      (node (ref "X5") (pin "8") (pinfunction "F_8") (pintype "passive"))
      (node (ref "X5") (pin "G1") (pinfunction "G1_G1") (pintype "passive"))
    )
    (net (code "65") (name "Net-(C1-Pad2)") (class "Default")
      (node (ref "C1") (pin "2") (pinfunction "2_2") (pintype "passive"))
      (node (ref "R23") (pin "2") (pinfunction "2_2") (pintype "passive"))
      (node (ref "R48") (pin "1") (pinfunction "1_1") (pintype "passive"))
    )
    (net (code "66") (name "Net-(C2-Pad1)") (class "Default")
      (node (ref "C2") (pin "1") (pinfunction "1_1") (pintype "passive"))
      (node (ref "R17") (pin "2") (pinfunction "2_2") (pintype "passive"))
      (node (ref "X1") (pin "1") (pinfunction "1_1") (pintype "passive"))
    )
    (net (code "67") (name "Net-(C3-Pad1)") (class "Default")
      (node (ref "C3") (pin "1") (pinfunction "1_1") (pintype "passive"))
      (node (ref "R48") (pin "2") (pinfunction "2_2") (pintype "passive"))
    )
    (net (code "68") (name "Net-(C4-Pad1)") (class "Default")
      (node (ref "C4") (pin "1") (pinfunction "1_1") (pintype "passive"))
      (node (ref "R49") (pin "2") (pinfunction "2_2") (pintype "passive"))
    )
    (net (code "69") (name "Net-(C5-Pad2)") (class "Default")
      (node (ref "C5") (pin "2") (pinfunction "2_2") (pintype "passive"))
      (node (ref "R34") (pin "2") (pinfunction "2_2") (pintype "passive"))
      (node (ref "R49") (pin "1") (pinfunction "1_1") (pintype "passive"))
    )
    (net (code "70") (name "Net-(IC1-CLK)") (class "Default")
      (node (ref "IC1") (pin "3") (pinfunction "CLK_3") (pintype "bidirectional"))
      (node (ref "U1") (pin "P72") (pinfunction "CCLK_P72") (pintype "bidirectional"))
    )
    (net (code "71") (name "Net-(IC1-TDO)") (class "Default")
      (node (ref "IC1") (pin "17") (pinfunction "TDO_17") (pintype "bidirectional"))
      (node (ref "R1") (pin "2") (pinfunction "2_2") (pintype "passive"))
    )
    (net (code "72") (name "Net-(IC1-{slash}CE)") (class "Default")
      (node (ref "IC1") (pin "10") (pinfunction "/CE_10") (pintype "bidirectional"))
      (node (ref "U1") (pin "P71") (pinfunction "DONE_P71") (pintype "bidirectional"))
    )
    (net (code "73") (name "Net-(IC1-{slash}CF)") (class "Default")
      (node (ref "IC1") (pin "7") (pinfunction "/CF_7") (pintype "bidirectional"))
      (node (ref "U1") (pin "P143") (pinfunction "PROG_B_P143") (pintype "bidirectional"))
    )
    (net (code "74") (name "Net-(Q5-B)") (class "Default")
      (node (ref "Q5") (pin "1") (pinfunction "B_1") (pintype "passive"))
      (node (ref "R8") (pin "2") (pinfunction "2_2") (pintype "passive"))
    )
    (net (code "75") (name "Net-(Q5-E)") (class "Default")
      (node (ref "Q5") (pin "2") (pinfunction "E_2") (pintype "passive"))
      (node (ref "R13") (pin "2") (pinfunction "2_2") (pintype "passive"))
      (node (ref "R14") (pin "2") (pinfunction "2_2") (pintype "passive"))
    )
    (net (code "76") (name "Net-(Q6-B)") (class "Default")
      (node (ref "Q6") (pin "1") (pinfunction "B_1") (pintype "passive"))
      (node (ref "R10") (pin "2") (pinfunction "2_2") (pintype "passive"))
      (node (ref "R9") (pin "2") (pinfunction "2_2") (pintype "passive"))
    )
    (net (code "77") (name "Net-(Q6-E)") (class "Default")
      (node (ref "Q6") (pin "2") (pinfunction "E_2") (pintype "passive"))
      (node (ref "R15") (pin "2") (pinfunction "2_2") (pintype "passive"))
      (node (ref "R16") (pin "2") (pinfunction "2_2") (pintype "passive"))
      (node (ref "R20") (pin "2") (pinfunction "2_2") (pintype "passive"))
    )
    (net (code "78") (name "Net-(Q7-B)") (class "Default")
      (node (ref "Q7") (pin "1") (pinfunction "B_1") (pintype "passive"))
      (node (ref "R29") (pin "2") (pinfunction "2_2") (pintype "passive"))
      (node (ref "R30") (pin "2") (pinfunction "2_2") (pintype "passive"))
    )
    (net (code "79") (name "Net-(Q7-E)") (class "Default")
      (node (ref "Q7") (pin "2") (pinfunction "E_2") (pintype "passive"))
      (node (ref "R31") (pin "2") (pinfunction "2_2") (pintype "passive"))
      (node (ref "R32") (pin "2") (pinfunction "2_2") (pintype "passive"))
      (node (ref "R33") (pin "2") (pinfunction "2_2") (pintype "passive"))
    )
    (net (code "80") (name "Net-(Q8-B)") (class "Default")
      (node (ref "Q8") (pin "1") (pinfunction "B_1") (pintype "passive"))
      (node (ref "R24") (pin "2") (pinfunction "2_2") (pintype "passive"))
      (node (ref "R25") (pin "2") (pinfunction "2_2") (pintype "passive"))
    )
    (net (code "81") (name "Net-(Q8-E)") (class "Default")
      (node (ref "Q8") (pin "2") (pinfunction "E_2") (pintype "passive"))
      (node (ref "R26") (pin "2") (pinfunction "2_2") (pintype "passive"))
      (node (ref "R27") (pin "2") (pinfunction "2_2") (pintype "passive"))
      (node (ref "R28") (pin "2") (pinfunction "2_2") (pintype "passive"))
    )
    (net (code "82") (name "Net-(R18-Pad2)") (class "Default")
      (node (ref "R18") (pin "2") (pinfunction "2_2") (pintype "passive"))
      (node (ref "R22") (pin "2") (pinfunction "2_2") (pintype "passive"))
    )
    (net (code "83") (name "Net-(T2-B)") (class "Default")
      (node (ref "C2") (pin "2") (pinfunction "2_2") (pintype "passive"))
      (node (ref "R18") (pin "1") (pinfunction "1_1") (pintype "passive"))
      (node (ref "R19") (pin "2") (pinfunction "2_2") (pintype "passive"))
      (node (ref "T2") (pin "1") (pinfunction "B_1") (pintype "passive"))
    )
    (net (code "84") (name "Net-(U$1-A0)") (class "Default")
      (node (ref "U$1") (pin "P20") (pinfunction "A0_P20") (pintype "bidirectional"))
      (node (ref "U1") (pin "P77") (pinfunction "IO_L20P_3_P77") (pintype "bidirectional"))
    )
    (net (code "85") (name "Net-(U$1-A1)") (class "Default")
      (node (ref "U$1") (pin "P19") (pinfunction "A1_P19") (pintype "bidirectional"))
      (node (ref "U1") (pin "P76") (pinfunction "IO_P76") (pintype "bidirectional"))
    )
    (net (code "86") (name "Net-(U$1-A2)") (class "Default")
      (node (ref "U$1") (pin "P18") (pinfunction "A2_P18") (pintype "bidirectional"))
      (node (ref "U1") (pin "P74") (pinfunction "IO_L01N_3VRP_3_P74") (pintype "bidirectional"))
    )
    (net (code "87") (name "Net-(U$1-A3)") (class "Default")
      (node (ref "U$1") (pin "P17") (pinfunction "A3_P17") (pintype "bidirectional"))
      (node (ref "U1") (pin "P73") (pinfunction "IO_L01P_3VRN_3_P73") (pintype "bidirectional"))
    )
    (net (code "88") (name "Net-(U$1-A4)") (class "Default")
      (node (ref "U$1") (pin "P16") (pinfunction "A4_P16") (pintype "bidirectional"))
      (node (ref "U1") (pin "P108") (pinfunction "IO_L01N_2VRP_2_P108") (pintype "bidirectional"))
    )
    (net (code "89") (name "Net-(U$1-A5)") (class "Default")
      (node (ref "U$1") (pin "P15") (pinfunction "A5_P15") (pintype "bidirectional"))
      (node (ref "U1") (pin "P107") (pinfunction "IO_L01P_2VRN_2_P107") (pintype "bidirectional"))
    )
    (net (code "90") (name "Net-(U$1-A6)") (class "Default")
      (node (ref "U$1") (pin "P14") (pinfunction "A6_P14") (pintype "bidirectional"))
      (node (ref "U1") (pin "P105") (pinfunction "IO_L20N_2_P105") (pintype "bidirectional"))
    )
    (net (code "91") (name "Net-(U$1-A7)") (class "Default")
      (node (ref "U$1") (pin "P13") (pinfunction "A7_P13") (pintype "bidirectional"))
      (node (ref "U1") (pin "P104") (pinfunction "IO_L20P_2_P104") (pintype "bidirectional"))
    )
    (net (code "92") (name "Net-(U$1-A8)") (class "Default")
      (node (ref "U$1") (pin "P3") (pinfunction "A8_P3") (pintype "bidirectional"))
      (node (ref "U1") (pin "P93") (pinfunction "IO_L40N_2_P93") (pintype "bidirectional"))
    )
    (net (code "93") (name "Net-(U$1-A9)") (class "Default")
      (node (ref "U$1") (pin "P2") (pinfunction "A9_P2") (pintype "bidirectional"))
      (node (ref "U1") (pin "P92") (pinfunction "IO_L40P_2VREF_2_P92") (pintype "bidirectional"))
    )
    (net (code "94") (name "Net-(U$1-A10)") (class "Default")
      (node (ref "U$1") (pin "P31") (pinfunction "A10_P31") (pintype "bidirectional"))
      (node (ref "U1") (pin "P87") (pinfunction "IO_L24N_3_P87") (pintype "bidirectional"))
    )
    (net (code "95") (name "Net-(U$1-A11)") (class "Default")
      (node (ref "U$1") (pin "P1") (pinfunction "A11_P1") (pintype "bidirectional"))
      (node (ref "U1") (pin "P90") (pinfunction "IO_L40N_3VREF_3_P90") (pintype "bidirectional"))
    )
    (net (code "96") (name "Net-(U$1-A12)") (class "Default")
      (node (ref "U$1") (pin "P12") (pinfunction "A12_P12") (pintype "bidirectional"))
      (node (ref "U1") (pin "P103") (pinfunction "IO_L21N_2_P103") (pintype "bidirectional"))
    )
    (net (code "97") (name "Net-(U$1-A13)") (class "Default")
      (node (ref "U$1") (pin "P4") (pinfunction "A13_P4") (pintype "bidirectional"))
      (node (ref "U1") (pin "P95") (pinfunction "IO_L24P_2_P95") (pintype "bidirectional"))
    )
    (net (code "98") (name "Net-(U$1-A14)") (class "Default")
      (node (ref "U$1") (pin "P11") (pinfunction "A14_P11") (pintype "bidirectional"))
      (node (ref "U1") (pin "P102") (pinfunction "IO_L21P_2_P102") (pintype "bidirectional"))
    )
    (net (code "99") (name "Net-(U$1-A15)") (class "Default")
      (node (ref "U$1") (pin "P7") (pinfunction "A15_P7") (pintype "bidirectional"))
      (node (ref "U1") (pin "P98") (pinfunction "IO_L23N_2VREF_2_P98") (pintype "bidirectional"))
    )
    (net (code "100") (name "Net-(U$1-A16)") (class "Default")
      (node (ref "U$1") (pin "P10") (pinfunction "A16_P10") (pintype "bidirectional"))
      (node (ref "U1") (pin "P100") (pinfunction "IO_L22N_2_P100") (pintype "bidirectional"))
    )
    (net (code "101") (name "Net-(U$1-A17)") (class "Default")
      (node (ref "U$1") (pin "P6") (pinfunction "A17_P6") (pintype "bidirectional"))
      (node (ref "U1") (pin "P97") (pinfunction "IO_L23P_2_P97") (pintype "bidirectional"))
    )
    (net (code "102") (name "Net-(U$1-A18)") (class "Default")
      (node (ref "U$1") (pin "P9") (pinfunction "A18_P9") (pintype "bidirectional"))
      (node (ref "U1") (pin "P99") (pinfunction "IO_L22P_2_P99") (pintype "bidirectional"))
    )
    (net (code "103") (name "Net-(U$1-DQ0)") (class "Default")
      (node (ref "U$1") (pin "P21") (pinfunction "DQ0_P21") (pintype "bidirectional"))
      (node (ref "U1") (pin "P78") (pinfunction "IO_L20N_3_P78") (pintype "bidirectional"))
    )
    (net (code "104") (name "Net-(U$1-DQ1)") (class "Default")
      (node (ref "U$1") (pin "P22") (pinfunction "DQ1_P22") (pintype "bidirectional"))
      (node (ref "U1") (pin "P79") (pinfunction "IO_L21P_3_P79") (pintype "bidirectional"))
    )
    (net (code "105") (name "Net-(U$1-DQ2)") (class "Default")
      (node (ref "U$1") (pin "P23") (pinfunction "DQ2_P23") (pintype "bidirectional"))
      (node (ref "U1") (pin "P80") (pinfunction "IO_L21N_3_P80") (pintype "bidirectional"))
    )
    (net (code "106") (name "Net-(U$1-DQ3)") (class "Default")
      (node (ref "U$1") (pin "P25") (pinfunction "DQ3_P25") (pintype "bidirectional"))
      (node (ref "U1") (pin "P82") (pinfunction "IO_L22P_3_P82") (pintype "bidirectional"))
    )
    (net (code "107") (name "Net-(U$1-DQ4)") (class "Default")
      (node (ref "U$1") (pin "P26") (pinfunction "DQ4_P26") (pintype "bidirectional"))
      (node (ref "U1") (pin "P83") (pinfunction "IO_L22N_3_P83") (pintype "bidirectional"))
    )
    (net (code "108") (name "Net-(U$1-DQ5)") (class "Default")
      (node (ref "U$1") (pin "P27") (pinfunction "DQ5_P27") (pintype "bidirectional"))
      (node (ref "U1") (pin "P84") (pinfunction "IO_L23P_3VREF_3_P84") (pintype "bidirectional"))
    )
    (net (code "109") (name "Net-(U$1-DQ6)") (class "Default")
      (node (ref "U$1") (pin "P28") (pinfunction "DQ6_P28") (pintype "bidirectional"))
      (node (ref "U1") (pin "P85") (pinfunction "IO_L23N_3_P85") (pintype "bidirectional"))
    )
    (net (code "110") (name "Net-(U$1-DQ7)") (class "Default")
      (node (ref "U$1") (pin "P29") (pinfunction "DQ7_P29") (pintype "bidirectional"))
      (node (ref "U1") (pin "P86") (pinfunction "IO_L24P_3_P86") (pintype "bidirectional"))
    )
    (net (code "111") (name "Net-(U$1-OE)") (class "Default")
      (node (ref "U$1") (pin "P32") (pinfunction "OE_P32") (pintype "bidirectional"))
      (node (ref "U1") (pin "P89") (pinfunction "IO_L40P_3_P89") (pintype "bidirectional"))
    )
    (net (code "112") (name "Net-(U$1-WE)") (class "Default")
      (node (ref "U$1") (pin "P5") (pinfunction "WE_P5") (pintype "bidirectional"))
      (node (ref "U1") (pin "P96") (pinfunction "IO_L24N_2_P96") (pintype "bidirectional"))
    )
    (net (code "113") (name "Net-(U1N-TCK)") (class "Default")
      (node (ref "R2") (pin "1") (pinfunction "1_1") (pintype "passive"))
      (node (ref "U1") (pin "P110") (pinfunction "TCK_P110") (pintype "bidirectional"))
    )
    (net (code "114") (name "Net-(U1N-TDI)") (class "Default")
      (node (ref "R1") (pin "1") (pinfunction "1_1") (pintype "passive"))
      (node (ref "U1") (pin "P144") (pinfunction "TDI_P144") (pintype "bidirectional"))
    )
    (net (code "115") (name "Net-(U1N-TMS)") (class "Default")
      (node (ref "R3") (pin "1") (pinfunction "1_1") (pintype "passive"))
      (node (ref "U1") (pin "P111") (pinfunction "TMS_P111") (pintype "bidirectional"))
    )
    (net (code "116") (name "Net-(X4A-F)") (class "Default")
      (node (ref "R40") (pin "2") (pinfunction "2_2") (pintype "passive"))
      (node (ref "X4") (pin "1") (pinfunction "F_1") (pintype "passive"))
    )
    (net (code "117") (name "Net-(X4B-F)") (class "Default")
      (node (ref "R41") (pin "2") (pinfunction "2_2") (pintype "passive"))
      (node (ref "X4") (pin "2") (pinfunction "F_2") (pintype "passive"))
    )
    (net (code "118") (name "Net-(X4C-F)") (class "Default")
      (node (ref "R42") (pin "2") (pinfunction "2_2") (pintype "passive"))
      (node (ref "X4") (pin "3") (pinfunction "F_3") (pintype "passive"))
    )
    (net (code "119") (name "Net-(X4D-F)") (class "Default")
      (node (ref "R43") (pin "2") (pinfunction "2_2") (pintype "passive"))
      (node (ref "X4") (pin "4") (pinfunction "F_4") (pintype "passive"))
    )
    (net (code "120") (name "Net-(X4F-F)") (class "Default")
      (node (ref "R44") (pin "2") (pinfunction "2_2") (pintype "passive"))
      (node (ref "X4") (pin "6") (pinfunction "F_6") (pintype "passive"))
    )
    (net (code "121") (name "Net-(X4G-F)") (class "Default")
      (node (ref "R45") (pin "2") (pinfunction "2_2") (pintype "passive"))
      (node (ref "X4") (pin "7") (pinfunction "F_7") (pintype "passive"))
    )
    (net (code "122") (name "Net-(X5A-F)") (class "Default")
      (node (ref "R46") (pin "1") (pinfunction "1_1") (pintype "passive"))
      (node (ref "X5") (pin "1") (pinfunction "F_1") (pintype "passive"))
    )
    (net (code "123") (name "Net-(X5B-F)") (class "Default")
      (node (ref "R39") (pin "1") (pinfunction "1_1") (pintype "passive"))
      (node (ref "X5") (pin "2") (pinfunction "F_2") (pintype "passive"))
    )
    (net (code "124") (name "Net-(X5C-F)") (class "Default")
      (node (ref "R38") (pin "1") (pinfunction "1_1") (pintype "passive"))
      (node (ref "X5") (pin "3") (pinfunction "F_3") (pintype "passive"))
    )
    (net (code "125") (name "Net-(X5D-F)") (class "Default")
      (node (ref "R37") (pin "1") (pinfunction "1_1") (pintype "passive"))
      (node (ref "X5") (pin "4") (pinfunction "F_4") (pintype "passive"))
    )
    (net (code "126") (name "Net-(X5F-F)") (class "Default")
      (node (ref "R36") (pin "1") (pinfunction "1_1") (pintype "passive"))
      (node (ref "X5") (pin "6") (pinfunction "F_6") (pintype "passive"))
    )
    (net (code "127") (name "Net-(X5G-F)") (class "Default")
      (node (ref "R35") (pin "1") (pinfunction "1_1") (pintype "passive"))
      (node (ref "X5") (pin "7") (pinfunction "F_7") (pintype "passive"))
    )
    (net (code "128") (name "unconnected-(IC1-NC.1-Pad2)") (class "Default")
      (node (ref "IC1") (pin "2") (pinfunction "NC.1_2") (pintype "bidirectional"))
    )
    (net (code "129") (name "unconnected-(IC1-NC.2-Pad9)") (class "Default")
      (node (ref "IC1") (pin "9") (pinfunction "NC.2_9") (pintype "bidirectional"))
    )
    (net (code "130") (name "unconnected-(IC1-NC.3-Pad12)") (class "Default")
      (node (ref "IC1") (pin "12") (pinfunction "NC.3_12") (pintype "bidirectional"))
    )
    (net (code "131") (name "unconnected-(IC1-NC.4-Pad14)") (class "Default")
      (node (ref "IC1") (pin "14") (pinfunction "NC.4_14") (pintype "bidirectional"))
    )
    (net (code "132") (name "unconnected-(IC1-NC.5-Pad15)") (class "Default")
      (node (ref "IC1") (pin "15") (pinfunction "NC.5_15") (pintype "bidirectional"))
    )
    (net (code "133") (name "unconnected-(IC1-NC.6-Pad16)") (class "Default")
      (node (ref "IC1") (pin "16") (pinfunction "NC.6_16") (pintype "bidirectional"))
    )
    (net (code "134") (name "unconnected-(IC1-{slash}CEO-Pad13)") (class "Default")
      (node (ref "IC1") (pin "13") (pinfunction "/CEO_13") (pintype "bidirectional"))
    )
    (net (code "135") (name "unconnected-(REG1.2-VOUT2-Pad2)") (class "Default")
      (node (ref "REG1.2") (pin "2") (pinfunction "VOUT2_2") (pintype "bidirectional"))
    )
    (net (code "136") (name "unconnected-(U$2-TRI-PadENA)") (class "Default")
      (node (ref "U$2") (pin "ENA") (pinfunction "TRI_ENA") (pintype "input"))
    )
    (net (code "137") (name "unconnected-(U$3-AREF-Pad42)") (class "Default")
      (node (ref "U$3") (pin "42") (pinfunction "AREF_42") (pintype "bidirectional"))
    )
    (net (code "138") (name "unconnected-(U$3-AVCC-Pad24)") (class "Default")
      (node (ref "U$3") (pin "24") (pinfunction "AVCC_24") (pintype "bidirectional"))
    )
    (net (code "139") (name "unconnected-(U$3-AVCC1-Pad44)") (class "Default")
      (node (ref "U$3") (pin "44") (pinfunction "AVCC1_44") (pintype "bidirectional"))
    )
    (net (code "140") (name "unconnected-(U$3-D+-Pad4)") (class "Default")
      (node (ref "U$3") (pin "4") (pinfunction "D+_4") (pintype "bidirectional"))
    )
    (net (code "141") (name "unconnected-(U$3-D--Pad3)") (class "Default")
      (node (ref "U$3") (pin "3") (pinfunction "D-_3") (pintype "bidirectional"))
    )
    (net (code "142") (name "unconnected-(U$3-GND-Pad15)") (class "Default")
      (node (ref "U$3") (pin "15") (pinfunction "GND_15") (pintype "bidirectional"))
    )
    (net (code "143") (name "unconnected-(U$3-GND1-Pad23)") (class "Default")
      (node (ref "U$3") (pin "23") (pinfunction "GND1_23") (pintype "bidirectional"))
    )
    (net (code "144") (name "unconnected-(U$3-GND2-Pad35)") (class "Default")
      (node (ref "U$3") (pin "35") (pinfunction "GND2_35") (pintype "bidirectional"))
    )
    (net (code "145") (name "unconnected-(U$3-GND3-Pad43)") (class "Default")
      (node (ref "U$3") (pin "43") (pinfunction "GND3_43") (pintype "bidirectional"))
    )
    (net (code "146") (name "unconnected-(U$3-PB4(ADC11)-Pad28)") (class "Default")
      (node (ref "U$3") (pin "28") (pinfunction "PB4(ADC11)_28") (pintype "bidirectional"))
    )
    (net (code "147") (name "unconnected-(U$3-PB5(OC1A{slash}ADC12{slash}~{OC4B})-Pad29)") (class "Default")
      (node (ref "U$3") (pin "29") (pinfunction "PB5(OC1A/ADC12/~{OC4B})_29") (pintype "bidirectional"))
    )
    (net (code "148") (name "unconnected-(U$3-PB6(OC1B{slash}OC4B{slash}ADC13)-Pad30)") (class "Default")
      (node (ref "U$3") (pin "30") (pinfunction "PB6(OC1B/OC4B/ADC13)_30") (pintype "bidirectional"))
    )
    (net (code "149") (name "unconnected-(U$3-PB7(OC0A{slash}OC1C{slash}RTS)-Pad12)") (class "Default")
      (node (ref "U$3") (pin "12") (pinfunction "PB7(OC0A/OC1C/RTS)_12") (pintype "bidirectional"))
    )
    (net (code "150") (name "unconnected-(U$3-PC6(OC3A{slash}~{OC4A})-Pad31)") (class "Default")
      (node (ref "U$3") (pin "31") (pinfunction "PC6(OC3A/~{OC4A})_31") (pintype "bidirectional"))
    )
    (net (code "151") (name "unconnected-(U$3-PC7(ICP3{slash}CLK0{slash}OC4A)-Pad32)") (class "Default")
      (node (ref "U$3") (pin "32") (pinfunction "PC7(ICP3/CLK0/OC4A)_32") (pintype "bidirectional"))
    )
    (net (code "152") (name "unconnected-(U$3-PD0(INT0{slash}OC0B{slash}SCL)-Pad18)") (class "Default")
      (node (ref "U$3") (pin "18") (pinfunction "PD0(INT0/OC0B/SCL)_18") (pintype "bidirectional"))
    )
    (net (code "153") (name "unconnected-(U$3-PD1(INT1{slash}SDA)-Pad19)") (class "Default")
      (node (ref "U$3") (pin "19") (pinfunction "PD1(INT1/SDA)_19") (pintype "bidirectional"))
    )
    (net (code "154") (name "unconnected-(U$3-PD2(INT2{slash}RXD1)-Pad20)") (class "Default")
      (node (ref "U$3") (pin "20") (pinfunction "PD2(INT2/RXD1)_20") (pintype "bidirectional"))
    )
    (net (code "155") (name "unconnected-(U$3-PD3(INT3{slash}TXD1)-Pad21)") (class "Default")
      (node (ref "U$3") (pin "21") (pinfunction "PD3(INT3/TXD1)_21") (pintype "bidirectional"))
    )
    (net (code "156") (name "unconnected-(U$3-PD4(ICP1{slash}ADC8)-Pad25)") (class "Default")
      (node (ref "U$3") (pin "25") (pinfunction "PD4(ICP1/ADC8)_25") (pintype "bidirectional"))
    )
    (net (code "157") (name "unconnected-(U$3-PD5(XCK{slash}CTS)-Pad22)") (class "Default")
      (node (ref "U$3") (pin "22") (pinfunction "PD5(XCK/CTS)_22") (pintype "bidirectional"))
    )
    (net (code "158") (name "unconnected-(U$3-PD6(T1{slash}ADC9{slash}~{OC4D})-Pad26)") (class "Default")
      (node (ref "U$3") (pin "26") (pinfunction "PD6(T1/ADC9/~{OC4D})_26") (pintype "bidirectional"))
    )
    (net (code "159") (name "unconnected-(U$3-PD7(OC4D{slash}ADC10{slash}T0)-Pad27)") (class "Default")
      (node (ref "U$3") (pin "27") (pinfunction "PD7(OC4D/ADC10/T0)_27") (pintype "bidirectional"))
    )
    (net (code "160") (name "unconnected-(U$3-PE2(~{HWB})-Pad33)") (class "Default")
      (node (ref "U$3") (pin "33") (pinfunction "PE2(~{HWB})_33") (pintype "bidirectional"))
    )
    (net (code "161") (name "unconnected-(U$3-PE6(INT.6{slash}AIN0)-Pad1)") (class "Default")
      (node (ref "U$3") (pin "1") (pinfunction "PE6(INT.6/AIN0)_1") (pintype "bidirectional"))
    )
    (net (code "162") (name "unconnected-(U$3-PF0(ADC0)-Pad41)") (class "Default")
      (node (ref "U$3") (pin "41") (pinfunction "PF0(ADC0)_41") (pintype "bidirectional"))
    )
    (net (code "163") (name "unconnected-(U$3-PF1(ADC1)-Pad40)") (class "Default")
      (node (ref "U$3") (pin "40") (pinfunction "PF1(ADC1)_40") (pintype "bidirectional"))
    )
    (net (code "164") (name "unconnected-(U$3-UCAP-Pad6)") (class "Default")
      (node (ref "U$3") (pin "6") (pinfunction "UCAP_6") (pintype "bidirectional"))
    )
    (net (code "165") (name "unconnected-(U$3-UGND-Pad5)") (class "Default")
      (node (ref "U$3") (pin "5") (pinfunction "UGND_5") (pintype "bidirectional"))
    )
    (net (code "166") (name "unconnected-(U$3-UVCC-Pad2)") (class "Default")
      (node (ref "U$3") (pin "2") (pinfunction "UVCC_2") (pintype "bidirectional"))
    )
    (net (code "167") (name "unconnected-(U$3-VBUS-Pad7)") (class "Default")
      (node (ref "U$3") (pin "7") (pinfunction "VBUS_7") (pintype "bidirectional"))
    )
    (net (code "168") (name "unconnected-(U$3-VCC-Pad14)") (class "Default")
      (node (ref "U$3") (pin "14") (pinfunction "VCC_14") (pintype "bidirectional"))
    )
    (net (code "169") (name "unconnected-(U$3-VCC1-Pad34)") (class "Default")
      (node (ref "U$3") (pin "34") (pinfunction "VCC1_34") (pintype "bidirectional"))
    )
    (net (code "170") (name "unconnected-(U$3-XTAL1-Pad17)") (class "Default")
      (node (ref "U$3") (pin "17") (pinfunction "XTAL1_17") (pintype "bidirectional"))
    )
    (net (code "171") (name "unconnected-(U$3-XTAL2-Pad16)") (class "Default")
      (node (ref "U$3") (pin "16") (pinfunction "XTAL2_16") (pintype "bidirectional"))
    )
    (net (code "172") (name "unconnected-(U$3-{slash}RESET-Pad13)") (class "Default")
      (node (ref "U$3") (pin "13") (pinfunction "/RESET_13") (pintype "bidirectional"))
    )
    (net (code "173") (name "unconnected-(U1A-IO_L27P_0-PadP135)") (class "Default")
      (node (ref "U1") (pin "P135") (pinfunction "IO_L27P_0_P135") (pintype "bidirectional"))
    )
    (net (code "174") (name "unconnected-(U1A-IO_L30N_0-PadP132)") (class "Default")
      (node (ref "U1") (pin "P132") (pinfunction "IO_L30N_0_P132") (pintype "bidirectional"))
    )
    (net (code "175") (name "unconnected-(U1A-IO_L30P_0-PadP131)") (class "Default")
      (node (ref "U1") (pin "P131") (pinfunction "IO_L30P_0_P131") (pintype "bidirectional"))
    )
    (net (code "176") (name "unconnected-(U1A-IO_L31N_0-PadP130)") (class "Default")
      (node (ref "U1") (pin "P130") (pinfunction "IO_L31N_0_P130") (pintype "bidirectional"))
    )
    (net (code "177") (name "unconnected-(U1A-IO_L31P_0VREF_0-PadP129)") (class "Default")
      (node (ref "U1") (pin "P129") (pinfunction "IO_L31P_0VREF_0_P129") (pintype "bidirectional"))
    )
    (net (code "178") (name "unconnected-(U1A-IO_L32N_0GCLK7-PadP128)") (class "Default")
      (node (ref "U1") (pin "P128") (pinfunction "IO_L32N_0GCLK7_P128") (pintype "bidirectional"))
    )
    (net (code "179") (name "unconnected-(U1A-IO_L32P_0GCLK6-PadP127)") (class "Default")
      (node (ref "U1") (pin "P127") (pinfunction "IO_L32P_0GCLK6_P127") (pintype "bidirectional"))
    )
    (net (code "180") (name "unconnected-(U1C-IO-PadP116)") (class "Default")
      (node (ref "U1") (pin "P116") (pinfunction "IO_P116") (pintype "bidirectional"))
    )
    (net (code "181") (name "unconnected-(U1C-IO_L01N_1VRP_1-PadP113)") (class "Default")
      (node (ref "U1") (pin "P113") (pinfunction "IO_L01N_1VRP_1_P113") (pintype "bidirectional"))
    )
    (net (code "182") (name "unconnected-(U1C-IO_L01P_1VRN_1-PadP112)") (class "Default")
      (node (ref "U1") (pin "P112") (pinfunction "IO_L01P_1VRN_1_P112") (pintype "bidirectional"))
    )
    (net (code "183") (name "unconnected-(U1C-IO_L28N_1-PadP119)") (class "Default")
      (node (ref "U1") (pin "P119") (pinfunction "IO_L28N_1_P119") (pintype "bidirectional"))
    )
    (net (code "184") (name "unconnected-(U1C-IO_L28P_1-PadP118)") (class "Default")
      (node (ref "U1") (pin "P118") (pinfunction "IO_L28P_1_P118") (pintype "bidirectional"))
    )
    (net (code "185") (name "unconnected-(U1C-IO_L31N_1VREF_1-PadP123)") (class "Default")
      (node (ref "U1") (pin "P123") (pinfunction "IO_L31N_1VREF_1_P123") (pintype "bidirectional"))
    )
    (net (code "186") (name "unconnected-(U1C-IO_L31P_1-PadP122)") (class "Default")
      (node (ref "U1") (pin "P122") (pinfunction "IO_L31P_1_P122") (pintype "bidirectional"))
    )
    (net (code "187") (name "unconnected-(U1C-IO_L32N_1GCLK5-PadP125)") (class "Default")
      (node (ref "U1") (pin "P125") (pinfunction "IO_L32N_1GCLK5_P125") (pintype "bidirectional"))
    )
    (net (code "188") (name "unconnected-(U1C-IO_L32P_1GCLK4-PadP124)") (class "Default")
      (node (ref "U1") (pin "P124") (pinfunction "IO_L32P_1GCLK4_P124") (pintype "bidirectional"))
    )
    (net (code "189") (name "unconnected-(U1J-IO_L01N_6VRP_6-PadP36)") (class "Default")
      (node (ref "U1") (pin "P36") (pinfunction "IO_L01N_6VRP_6_P36") (pintype "bidirectional"))
    )
    (net (code "190") (name "unconnected-(U1J-IO_L01P_6VRN_6-PadP35)") (class "Default")
      (node (ref "U1") (pin "P35") (pinfunction "IO_L01P_6VRN_6_P35") (pintype "bidirectional"))
    )
    (net (code "191") (name "unconnected-(U1J-IO_L20N_6-PadP33)") (class "Default")
      (node (ref "U1") (pin "P33") (pinfunction "IO_L20N_6_P33") (pintype "bidirectional"))
    )
    (net (code "192") (name "unconnected-(U1J-IO_L20P_6-PadP32)") (class "Default")
      (node (ref "U1") (pin "P32") (pinfunction "IO_L20P_6_P32") (pintype "bidirectional"))
    )
    (net (code "193") (name "unconnected-(U1J-IO_L21N_6-PadP31)") (class "Default")
      (node (ref "U1") (pin "P31") (pinfunction "IO_L21N_6_P31") (pintype "bidirectional"))
    )
    (net (code "194") (name "unconnected-(U1J-IO_L21P_6-PadP30)") (class "Default")
      (node (ref "U1") (pin "P30") (pinfunction "IO_L21P_6_P30") (pintype "bidirectional"))
    )
    (net (code "195") (name "unconnected-(U1J-IO_L22N_6-PadP28)") (class "Default")
      (node (ref "U1") (pin "P28") (pinfunction "IO_L22N_6_P28") (pintype "bidirectional"))
    )
    (net (code "196") (name "unconnected-(U1J-IO_L22P_6-PadP27)") (class "Default")
      (node (ref "U1") (pin "P27") (pinfunction "IO_L22P_6_P27") (pintype "bidirectional"))
    )
    (net (code "197") (name "unconnected-(U1J-IO_L23N_6-PadP26)") (class "Default")
      (node (ref "U1") (pin "P26") (pinfunction "IO_L23N_6_P26") (pintype "bidirectional"))
    )
    (net (code "198") (name "unconnected-(U1J-IO_L23P_6-PadP25)") (class "Default")
      (node (ref "U1") (pin "P25") (pinfunction "IO_L23P_6_P25") (pintype "bidirectional"))
    )
    (net (code "199") (name "unconnected-(U1J-IO_L24N_6VREF_6-PadP24)") (class "Default")
      (node (ref "U1") (pin "P24") (pinfunction "IO_L24N_6VREF_6_P24") (pintype "bidirectional"))
    )
    (net (code "200") (name "unconnected-(U1J-IO_L24P_6-PadP23)") (class "Default")
      (node (ref "U1") (pin "P23") (pinfunction "IO_L24P_6_P23") (pintype "bidirectional"))
    )
    (net (code "201") (name "unconnected-(U1J-IO_L40N_6-PadP21)") (class "Default")
      (node (ref "U1") (pin "P21") (pinfunction "IO_L40N_6_P21") (pintype "bidirectional"))
    )
    (net (code "202") (name "unconnected-(U1J-IO_L40P_6VREF_6-PadP20)") (class "Default")
      (node (ref "U1") (pin "P20") (pinfunction "IO_L40P_6VREF_6_P20") (pintype "bidirectional"))
    )
    (net (code "203") (name "unconnected-(U1L-IOVREF_7-PadP4)") (class "Default")
      (node (ref "U1") (pin "P4") (pinfunction "IOVREF_7_P4") (pintype "bidirectional"))
    )
    (net (code "204") (name "unconnected-(U1L-IO_L01N_7VRP_7-PadP2)") (class "Default")
      (node (ref "U1") (pin "P2") (pinfunction "IO_L01N_7VRP_7_P2") (pintype "bidirectional"))
    )
    (net (code "205") (name "unconnected-(U1L-IO_L01P_7VRN_7-PadP1)") (class "Default")
      (node (ref "U1") (pin "P1") (pinfunction "IO_L01P_7VRN_7_P1") (pintype "bidirectional"))
    )
    (net (code "206") (name "unconnected-(U1L-IO_L20N_7-PadP6)") (class "Default")
      (node (ref "U1") (pin "P6") (pinfunction "IO_L20N_7_P6") (pintype "bidirectional"))
    )
    (net (code "207") (name "unconnected-(U1L-IO_L20P_7-PadP5)") (class "Default")
      (node (ref "U1") (pin "P5") (pinfunction "IO_L20P_7_P5") (pintype "bidirectional"))
    )
    (net (code "208") (name "unconnected-(U1L-IO_L21N_7-PadP8)") (class "Default")
      (node (ref "U1") (pin "P8") (pinfunction "IO_L21N_7_P8") (pintype "bidirectional"))
    )
    (net (code "209") (name "unconnected-(U1L-IO_L21P_7-PadP7)") (class "Default")
      (node (ref "U1") (pin "P7") (pinfunction "IO_L21P_7_P7") (pintype "bidirectional"))
    )
    (net (code "210") (name "unconnected-(U1L-IO_L22N_7-PadP11)") (class "Default")
      (node (ref "U1") (pin "P11") (pinfunction "IO_L22N_7_P11") (pintype "bidirectional"))
    )
    (net (code "211") (name "unconnected-(U1L-IO_L22P_7-PadP10)") (class "Default")
      (node (ref "U1") (pin "P10") (pinfunction "IO_L22P_7_P10") (pintype "bidirectional"))
    )
    (net (code "212") (name "unconnected-(U1L-IO_L23N_7-PadP13)") (class "Default")
      (node (ref "U1") (pin "P13") (pinfunction "IO_L23N_7_P13") (pintype "bidirectional"))
    )
    (net (code "213") (name "unconnected-(U1L-IO_L23P_7-PadP12)") (class "Default")
      (node (ref "U1") (pin "P12") (pinfunction "IO_L23P_7_P12") (pintype "bidirectional"))
    )
    (net (code "214") (name "unconnected-(U1L-IO_L24N_7-PadP15)") (class "Default")
      (node (ref "U1") (pin "P15") (pinfunction "IO_L24N_7_P15") (pintype "bidirectional"))
    )
    (net (code "215") (name "unconnected-(U1L-IO_L24P_7-PadP14)") (class "Default")
      (node (ref "U1") (pin "P14") (pinfunction "IO_L24P_7_P14") (pintype "bidirectional"))
    )
    (net (code "216") (name "unconnected-(U1L-IO_L40N_7VREF_7-PadP18)") (class "Default")
      (node (ref "U1") (pin "P18") (pinfunction "IO_L40N_7VREF_7_P18") (pintype "bidirectional"))
    )
    (net (code "217") (name "unconnected-(U1L-IO_L40P_7-PadP17)") (class "Default")
      (node (ref "U1") (pin "P17") (pinfunction "IO_L40P_7_P17") (pintype "bidirectional"))
    )
    (net (code "218") (name "unconnected-(U1N-HSWAP_EN-PadP142)") (class "Default")
      (node (ref "U1") (pin "P142") (pinfunction "HSWAP_EN_P142") (pintype "bidirectional"))
    )
    (net (code "219") (name "unconnected-(X1-3-Pad2)") (class "Default")
      (node (ref "X1") (pin "2") (pinfunction "3_2") (pintype "passive"))
    )
    (net (code "220") (name "unconnected-(X2-Pad10)") (class "Default")
      (node (ref "X2") (pin "10") (pinfunction "10_10") (pintype "passive"))
    )
    (net (code "221") (name "unconnected-(X2-Pad12)") (class "Default")
      (node (ref "X2") (pin "12") (pinfunction "12_12") (pintype "passive"))
    )
    (net (code "222") (name "unconnected-(X3-Pad2)") (class "Default")
      (node (ref "X3") (pin "2") (pinfunction "2_2") (pintype "passive"))
    )
    (net (code "223") (name "unconnected-(X3-Pad8)") (class "Default")
      (node (ref "X3") (pin "8") (pinfunction "8_8") (pintype "passive"))
    )
    (net (code "224") (name "unconnected-(X4-PadG2)") (class "Default")
      (node (ref "X4") (pin "G2") (pinfunction "G2_G2") (pintype "passive"))
    )
    (net (code "225") (name "unconnected-(X5-PadG2)") (class "Default")
      (node (ref "X5") (pin "G2") (pinfunction "G2_G2") (pintype "passive"))
    )
  )
)
